# Schematics_5.net
KiCad netlist of a schematic drawn in Altium Designer
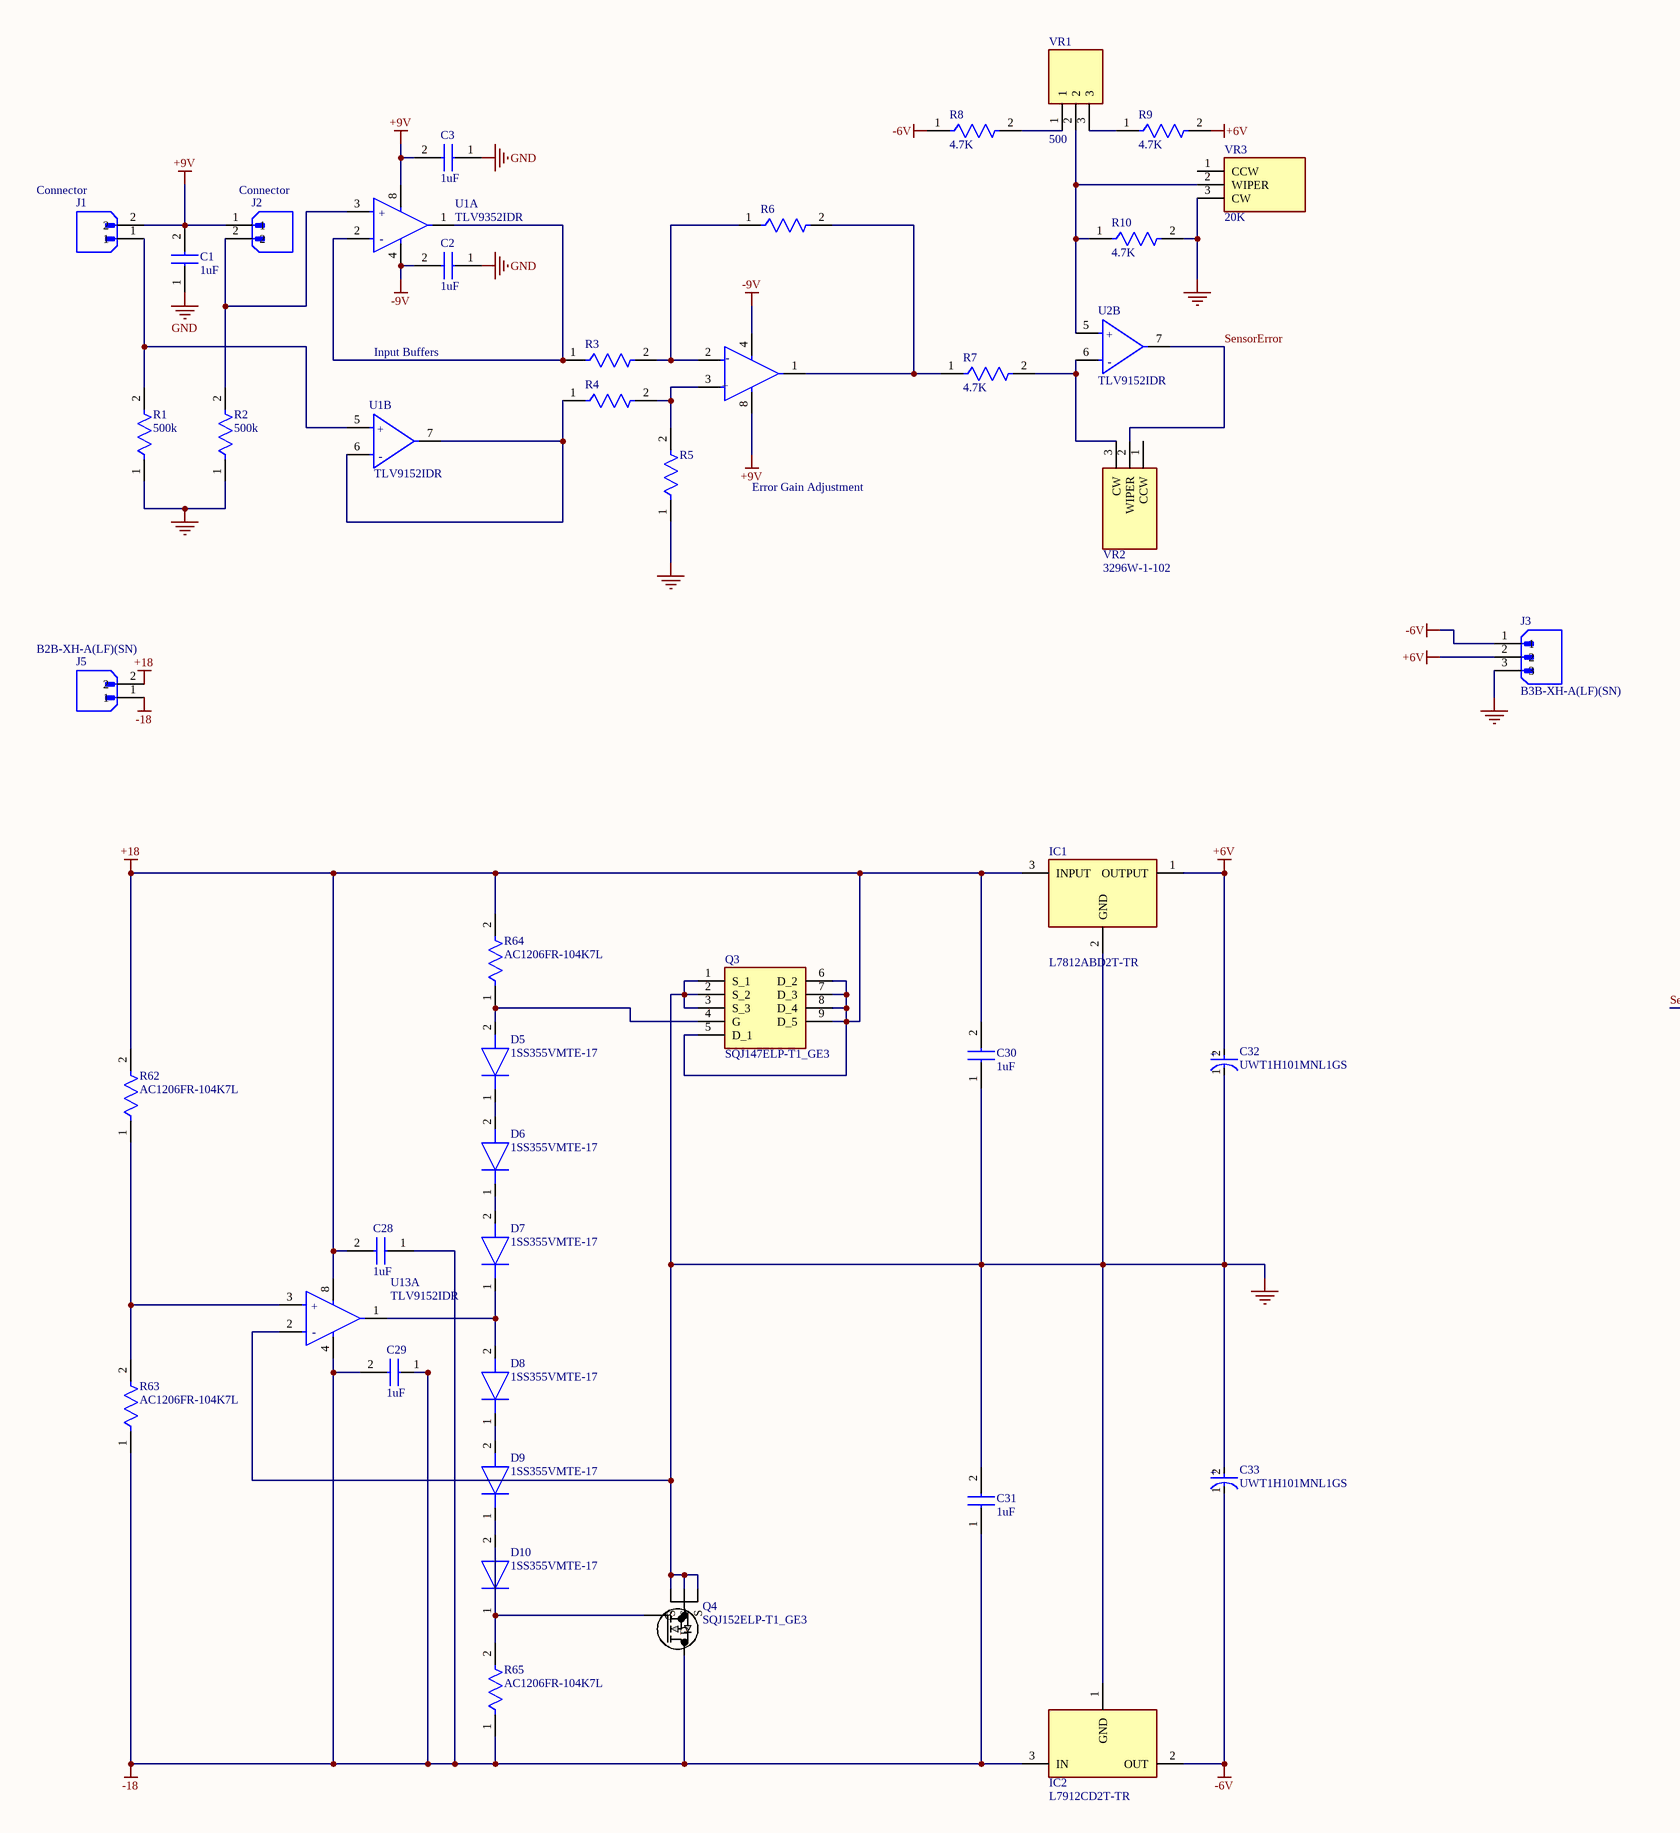
[diagram p0: Schematics_5.SchDoc, top left]
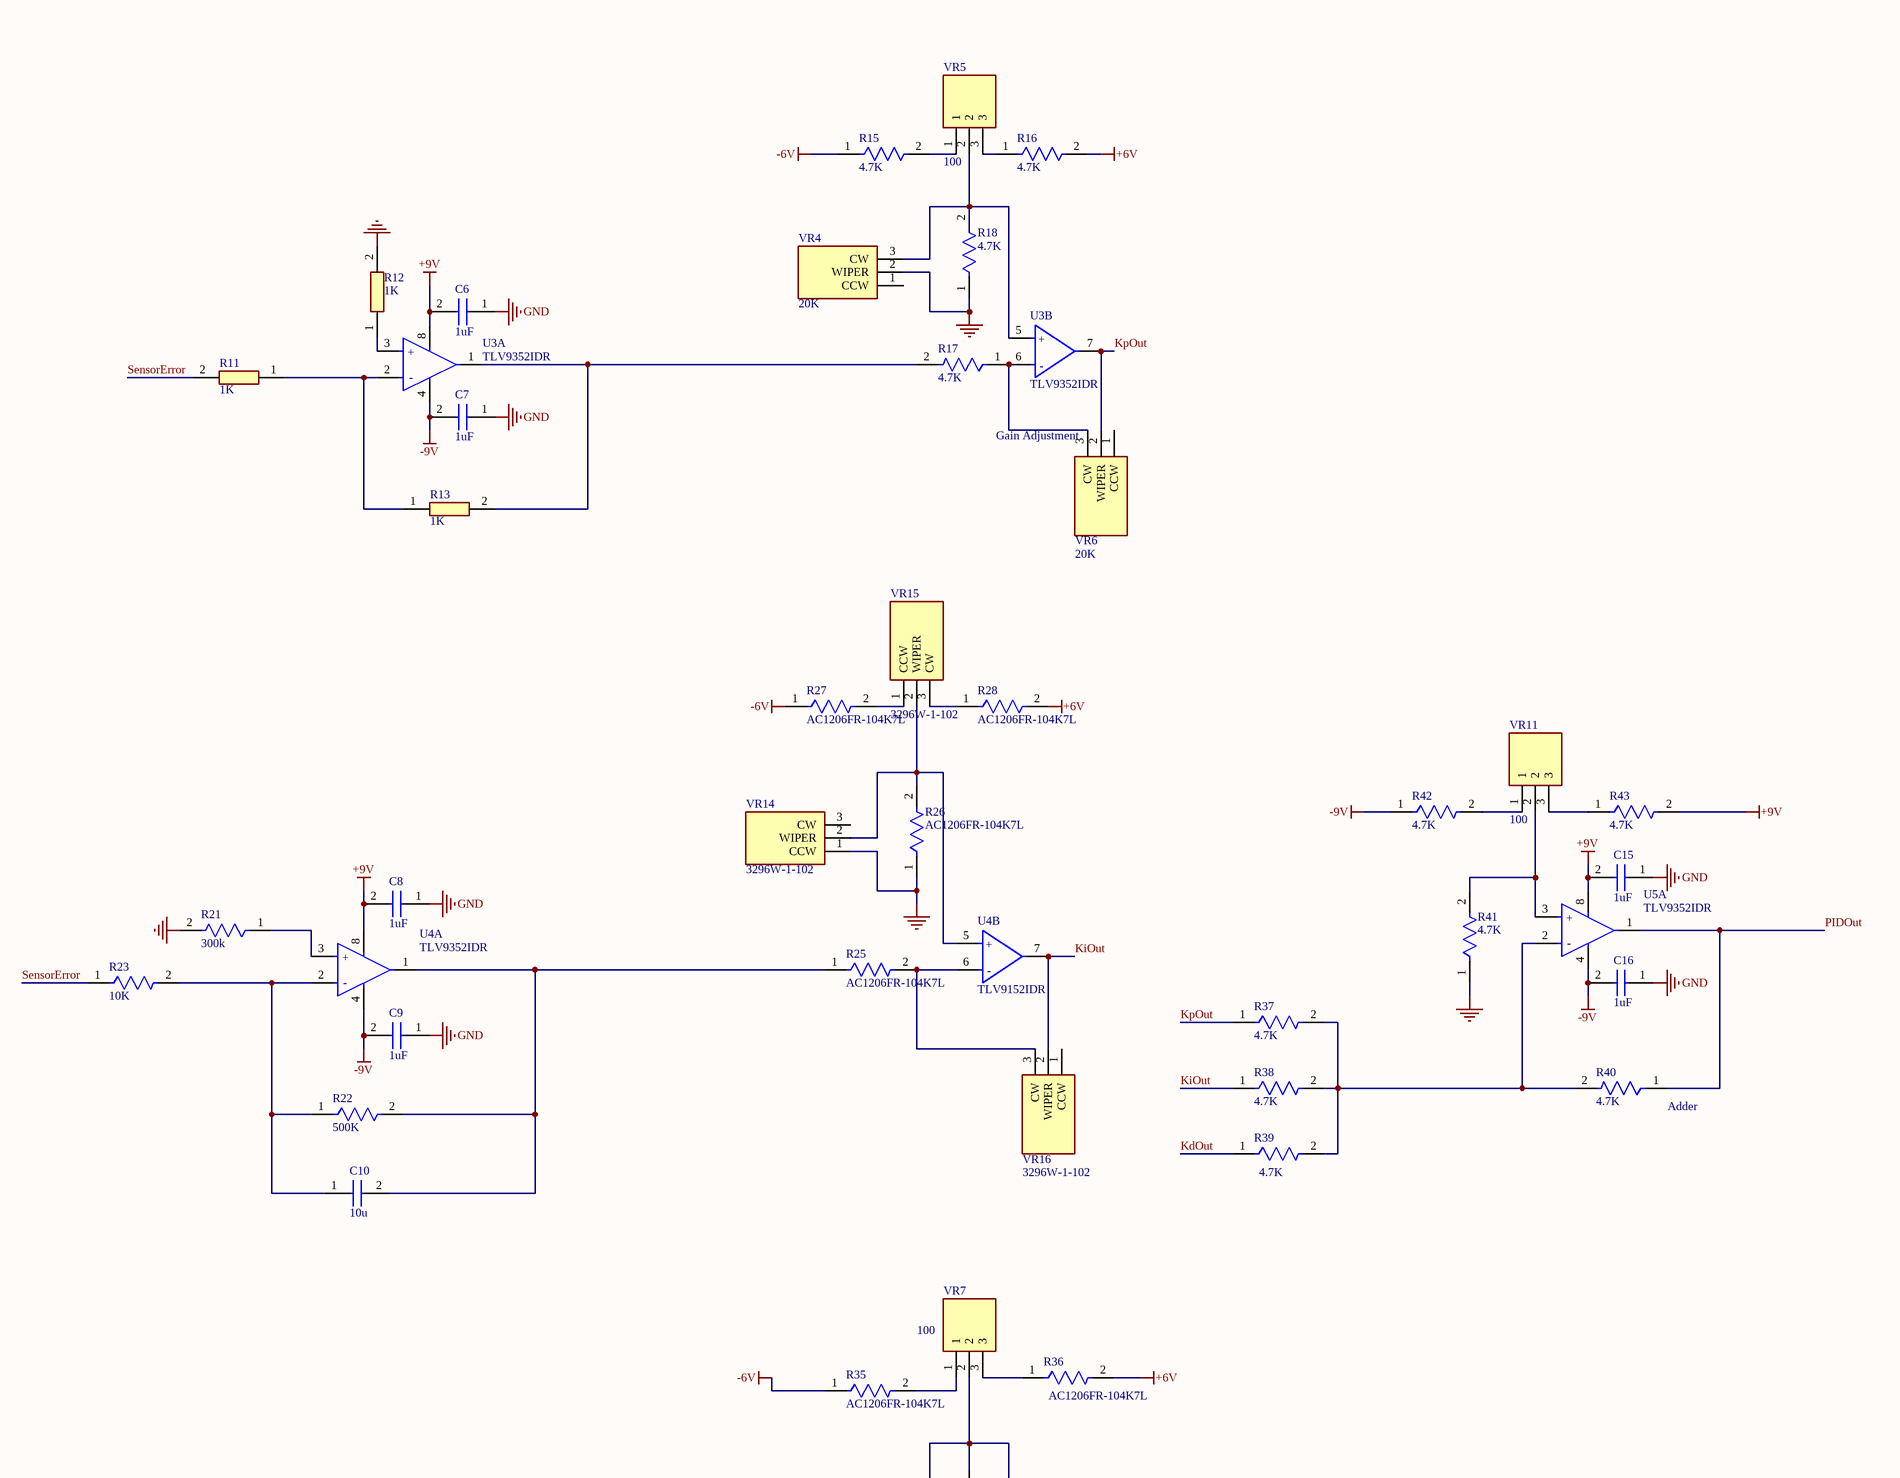
[diagram p1: Schematics_5.SchDoc, top right]
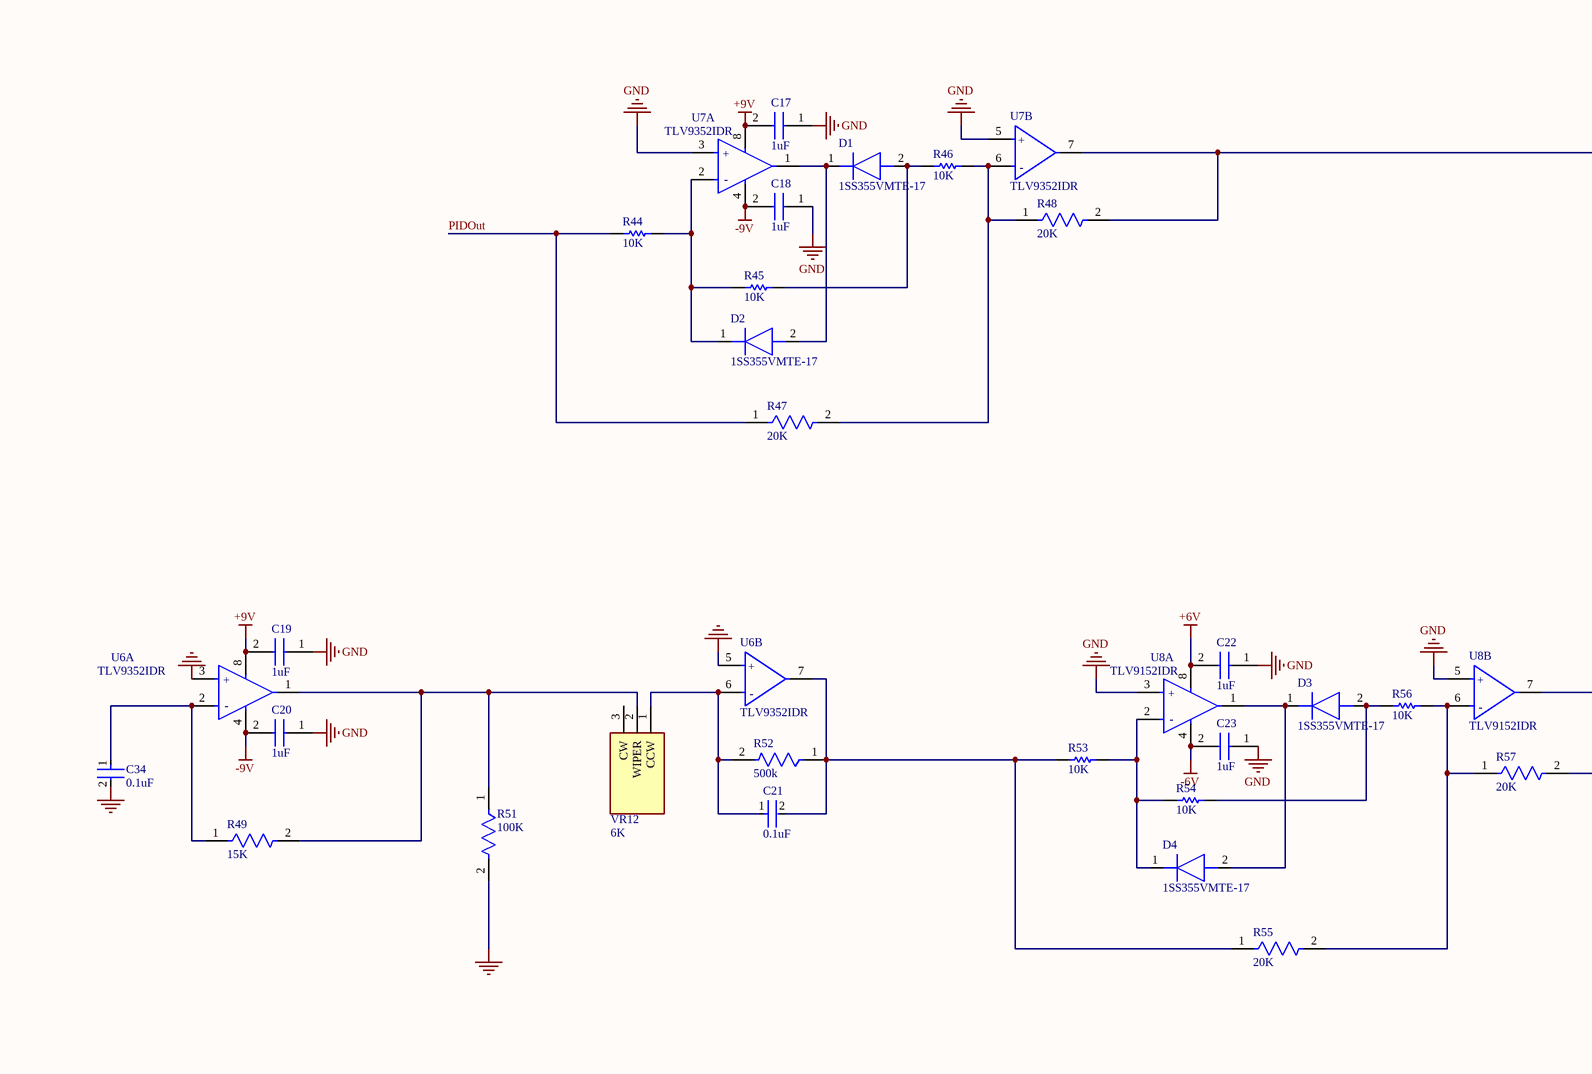
[diagram p2: Schematics_5.SchDoc, bottom left]
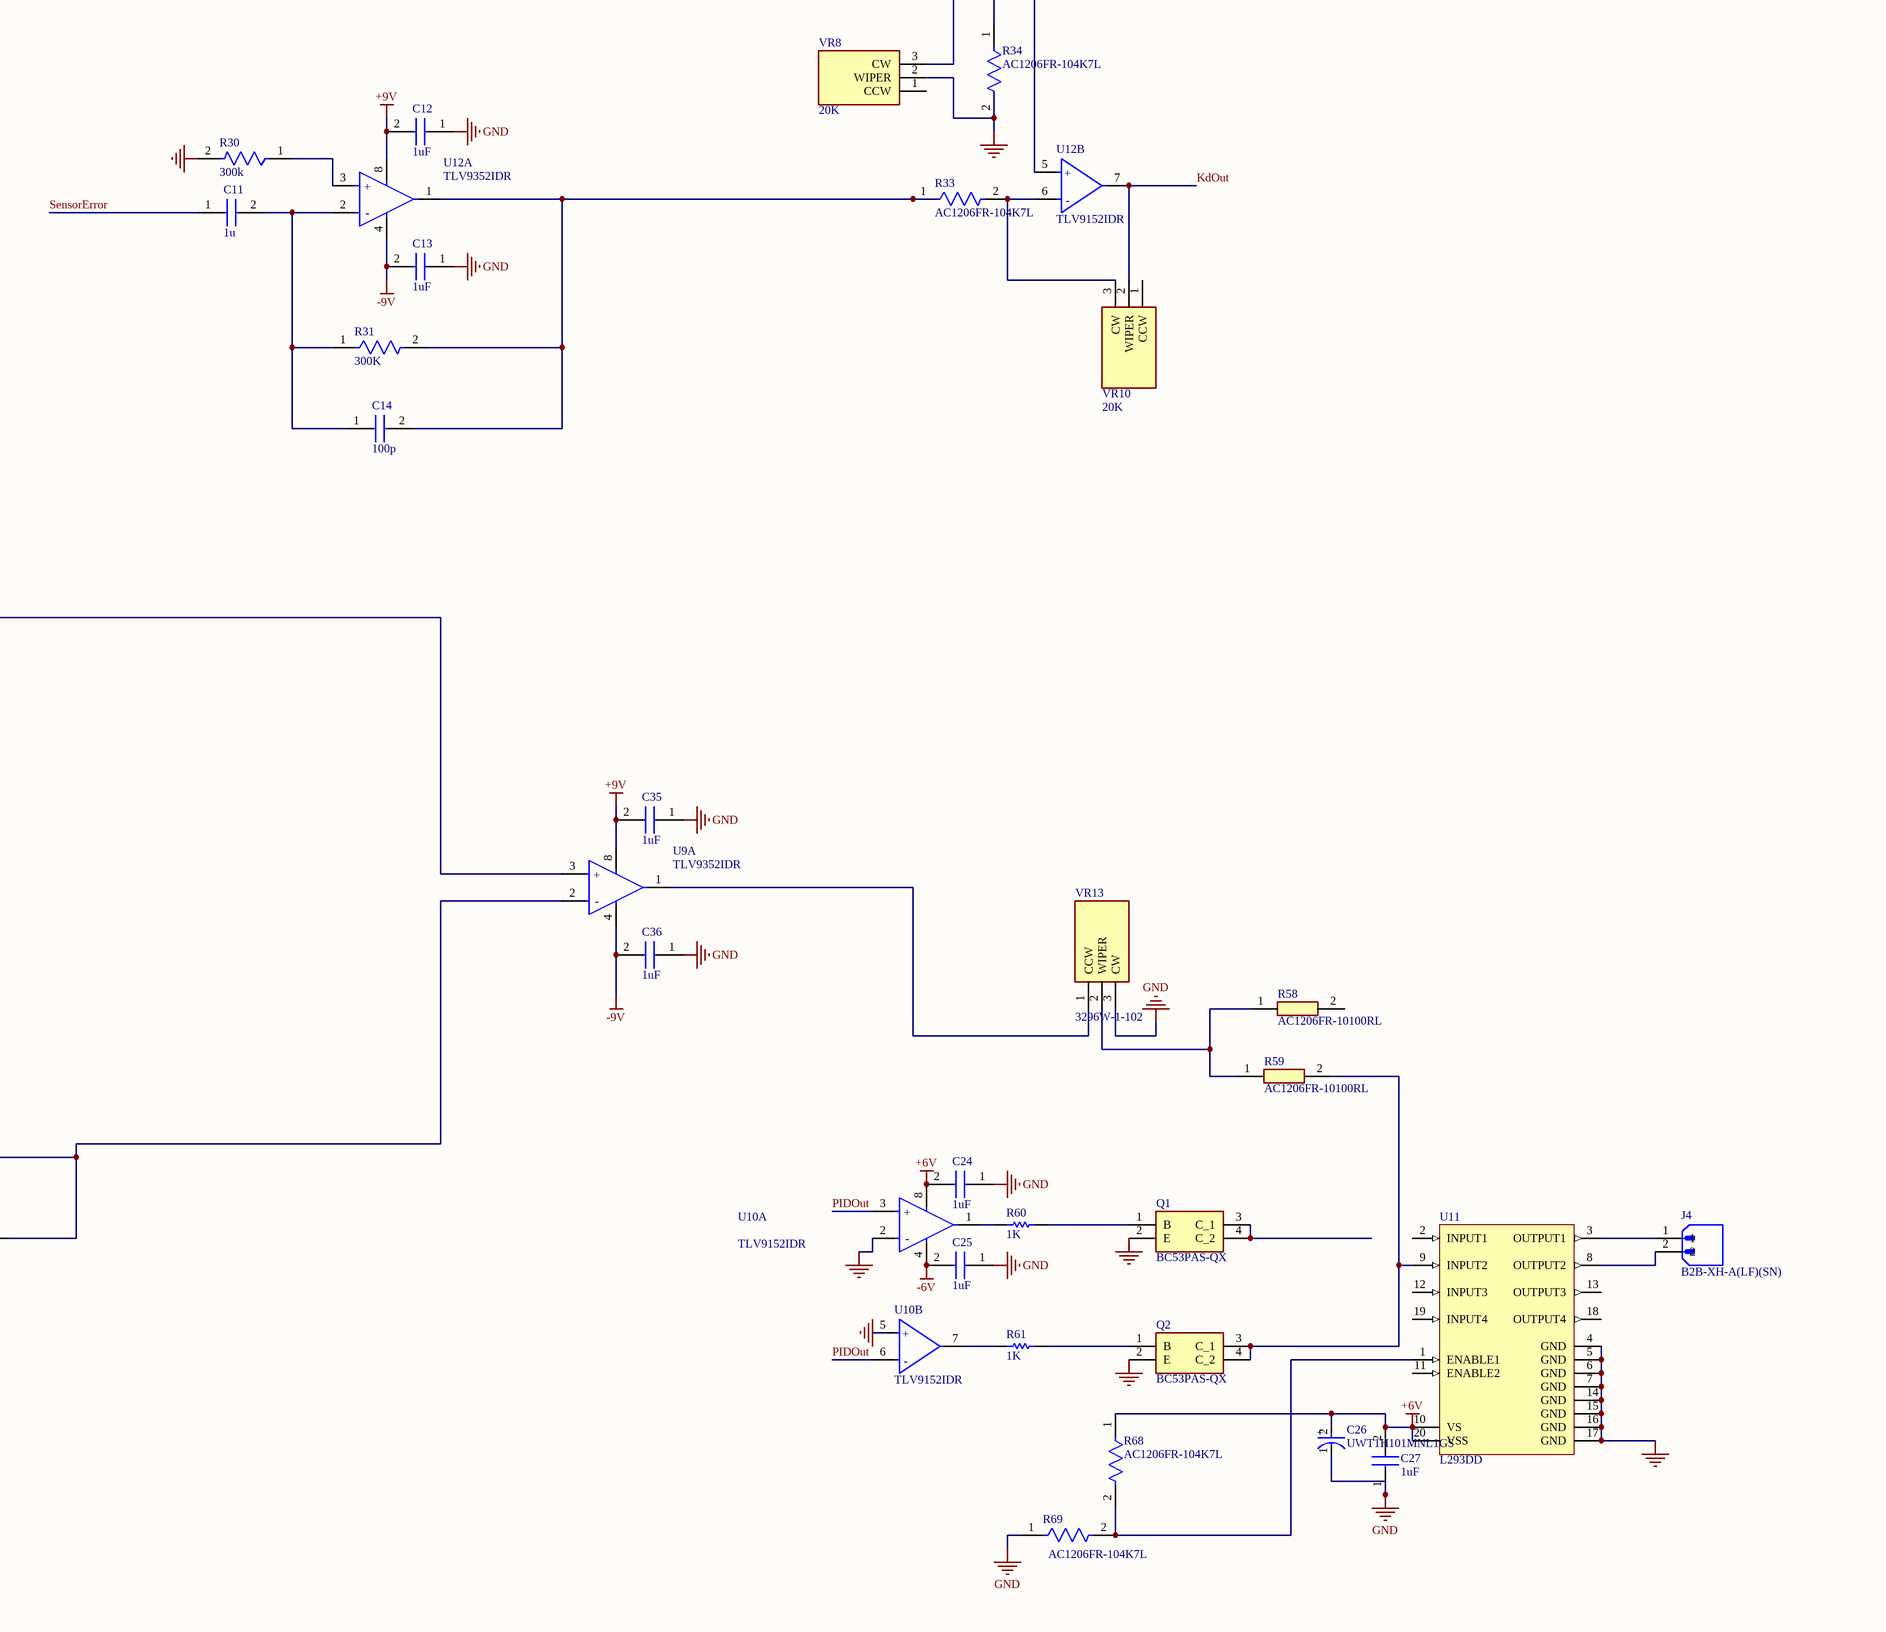
[diagram p3: Schematics_5.SchDoc, bottom right]

(export (version "E")
  (design (tool "Eeschema 10.0.6"))
  (components
    (comp (ref "C1")
      (value "1uF")
      (footprint "SamacSys:CAPC3216X178N")
      (description "Capacitor 12063C105MAT2A")
      (fields
        (field (name "MANUFACTURER_PART_NUMBER") "12063C105MAT2A")
        (field (name "MOUSER PART NUMBER") "581-12063C105MAT2A")
      )
      (libsource (lib "*") (part "12063C105MAT2A"))
    )
    (comp (ref "C2")
      (value "1uF")
      (footprint "SamacSys:CAPC3216X178N")
      (description "Capacitor 12063C105MAT2A")
      (fields
        (field (name "MANUFACTURER_PART_NUMBER") "12063C105MAT2A")
        (field (name "MOUSER PART NUMBER") "581-12063C105MAT2A")
      )
      (libsource (lib "*") (part "12063C105MAT2A"))
    )
    (comp (ref "C3")
      (value "1uF")
      (footprint "SamacSys:CAPC3216X178N")
      (description "Capacitor 12063C105MAT2A")
      (fields
        (field (name "MANUFACTURER_PART_NUMBER") "12063C105MAT2A")
        (field (name "MOUSER PART NUMBER") "581-12063C105MAT2A")
      )
      (libsource (lib "*") (part "12063C105MAT2A"))
    )
    (comp (ref "C6")
      (value "1uF")
      (footprint "SamacSys:CAPC3216X178N")
      (description "Capacitor 12063C105MAT2A")
      (fields
        (field (name "MANUFACTURER_PART_NUMBER") "12063C105MAT2A")
        (field (name "MOUSER PART NUMBER") "581-12063C105MAT2A")
      )
      (libsource (lib "*") (part "12063C105MAT2A"))
    )
    (comp (ref "C7")
      (value "1uF")
      (footprint "SamacSys:CAPC3216X178N")
      (description "Capacitor 12063C105MAT2A")
      (fields
        (field (name "MANUFACTURER_PART_NUMBER") "12063C105MAT2A")
        (field (name "MOUSER PART NUMBER") "581-12063C105MAT2A")
      )
      (libsource (lib "*") (part "12063C105MAT2A"))
    )
    (comp (ref "C8")
      (value "1uF")
      (footprint "SamacSys:CAPC3216X178N")
      (description "Capacitor 12063C105MAT2A")
      (fields
        (field (name "MANUFACTURER_PART_NUMBER") "12063C105MAT2A")
        (field (name "MOUSER PART NUMBER") "581-12063C105MAT2A")
      )
      (libsource (lib "*") (part "12063C105MAT2A"))
    )
    (comp (ref "C9")
      (value "1uF")
      (footprint "SamacSys:CAPC3216X178N")
      (description "Capacitor 12063C105MAT2A")
      (fields
        (field (name "MANUFACTURER_PART_NUMBER") "12063C105MAT2A")
        (field (name "MOUSER PART NUMBER") "581-12063C105MAT2A")
      )
      (libsource (lib "*") (part "12063C105MAT2A"))
    )
    (comp (ref "C10")
      (value "10u")
      (footprint "SamacSys:CAPC3216X170N")
      (description "Capacitor")
      (fields
        (field (name "MANUFACTURER_PART_NUMBER") "VJ1206A101JXEAT")
        (field (name "MOUSER PART NUMBER") "77-VJ1206A101JXEAT")
      )
      (libsource (lib "SamacSys") (part "VJ1206A101JXEAT"))
    )
    (comp (ref "C11")
      (value "1u")
      (footprint "SamacSys:C1206_FT")
      (description "Capacitor")
      (fields
        (field (name "MANUFACTURER_PART_NUMBER") "C1206X105J1RACTU")
        (field (name "MOUSER PART NUMBER") "80-C1206X105J1R")
      )
      (libsource (lib "*") (part "C1206X105J1RACTU"))
    )
    (comp (ref "C12")
      (value "1uF")
      (footprint "SamacSys:CAPC3216X178N")
      (description "Capacitor 12063C105MAT2A")
      (fields
        (field (name "MANUFACTURER_PART_NUMBER") "12063C105MAT2A")
        (field (name "MOUSER PART NUMBER") "581-12063C105MAT2A")
      )
      (libsource (lib "*") (part "12063C105MAT2A"))
    )
    (comp (ref "C13")
      (value "1uF")
      (footprint "SamacSys:CAPC3216X178N")
      (description "Capacitor 12063C105MAT2A")
      (fields
        (field (name "MANUFACTURER_PART_NUMBER") "12063C105MAT2A")
        (field (name "MOUSER PART NUMBER") "581-12063C105MAT2A")
      )
      (libsource (lib "*") (part "12063C105MAT2A"))
    )
    (comp (ref "C14")
      (value "100p")
      (footprint "SamacSys:CAPC3216X170N")
      (description "Capacitor")
      (fields
        (field (name "MANUFACTURER_PART_NUMBER") "VJ1206A101JXEAT")
        (field (name "MOUSER PART NUMBER") "77-VJ1206A101JXEAT")
      )
      (libsource (lib "*") (part "VJ1206A101JXEAT"))
    )
    (comp (ref "C15")
      (value "1uF")
      (footprint "SamacSys:CAPC3216X178N")
      (description "Capacitor 12063C105MAT2A")
      (fields
        (field (name "MANUFACTURER_PART_NUMBER") "12063C105MAT2A")
        (field (name "MOUSER PART NUMBER") "581-12063C105MAT2A")
      )
      (libsource (lib "*") (part "12063C105MAT2A"))
    )
    (comp (ref "C16")
      (value "1uF")
      (footprint "SamacSys:CAPC3216X178N")
      (description "Capacitor 12063C105MAT2A")
      (fields
        (field (name "MANUFACTURER_PART_NUMBER") "12063C105MAT2A")
        (field (name "MOUSER PART NUMBER") "581-12063C105MAT2A")
      )
      (libsource (lib "*") (part "12063C105MAT2A"))
    )
    (comp (ref "C17")
      (value "1uF")
      (footprint "SamacSys:CAPC3216X178N")
      (description "Capacitor 12063C105MAT2A")
      (fields
        (field (name "MANUFACTURER_PART_NUMBER") "12063C105MAT2A")
        (field (name "MOUSER PART NUMBER") "581-12063C105MAT2A")
      )
      (libsource (lib "*") (part "12063C105MAT2A"))
    )
    (comp (ref "C18")
      (value "1uF")
      (footprint "SamacSys:CAPC3216X178N")
      (description "Capacitor 12063C105MAT2A")
      (fields
        (field (name "MANUFACTURER_PART_NUMBER") "12063C105MAT2A")
        (field (name "MOUSER PART NUMBER") "581-12063C105MAT2A")
      )
      (libsource (lib "*") (part "12063C105MAT2A"))
    )
    (comp (ref "C19")
      (value "1uF")
      (footprint "SamacSys:CAPC3216X178N")
      (description "Capacitor 12063C105MAT2A")
      (fields
        (field (name "MANUFACTURER_PART_NUMBER") "12063C105MAT2A")
        (field (name "MOUSER PART NUMBER") "581-12063C105MAT2A")
      )
      (libsource (lib "*") (part "12063C105MAT2A"))
    )
    (comp (ref "C20")
      (value "1uF")
      (footprint "SamacSys:CAPC3216X178N")
      (description "Capacitor 12063C105MAT2A")
      (fields
        (field (name "MANUFACTURER_PART_NUMBER") "12063C105MAT2A")
        (field (name "MOUSER PART NUMBER") "581-12063C105MAT2A")
      )
      (libsource (lib "*") (part "12063C105MAT2A"))
    )
    (comp (ref "C21")
      (value "0.1uF")
      (footprint "FP-C1206C-EB-MFG")
      (description "CAP CER 0.1UF 25V C0G/NP0 1206")
      (fields
        (field (name "MANUFACTURER") "KEMET")
        (field (name "MANUFACTURER PART NUMBER") "C1206C104F3GACTU")
      )
      (libsource (lib "Altium Content Vault") (part "b4654b650e69147ec39a6b967a45e02"))
    )
    (comp (ref "C22")
      (value "1uF")
      (footprint "SamacSys:CAPC3216X178N")
      (description "Capacitor 12063C105MAT2A")
      (fields
        (field (name "MANUFACTURER_PART_NUMBER") "12063C105MAT2A")
        (field (name "MOUSER PART NUMBER") "581-12063C105MAT2A")
      )
      (libsource (lib "*") (part "12063C105MAT2A"))
    )
    (comp (ref "C23")
      (value "1uF")
      (footprint "SamacSys:CAPC3216X178N")
      (description "Capacitor 12063C105MAT2A")
      (fields
        (field (name "MANUFACTURER_PART_NUMBER") "12063C105MAT2A")
        (field (name "MOUSER PART NUMBER") "581-12063C105MAT2A")
      )
      (libsource (lib "*") (part "12063C105MAT2A"))
    )
    (comp (ref "C24")
      (value "1uF")
      (footprint "SamacSys:CAPC3216X178N")
      (description "Capacitor 12063C105MAT2A")
      (fields
        (field (name "MANUFACTURER_PART_NUMBER") "12063C105MAT2A")
        (field (name "MOUSER PART NUMBER") "581-12063C105MAT2A")
      )
      (libsource (lib "*") (part "12063C105MAT2A"))
    )
    (comp (ref "C25")
      (value "1uF")
      (footprint "SamacSys:CAPC3216X178N")
      (description "Capacitor 12063C105MAT2A")
      (fields
        (field (name "MANUFACTURER_PART_NUMBER") "12063C105MAT2A")
        (field (name "MOUSER PART NUMBER") "581-12063C105MAT2A")
      )
      (libsource (lib "*") (part "12063C105MAT2A"))
    )
    (comp (ref "C26")
      (value "UWT1H101MNL1GS")
      (footprint "FP-UWT1H101MNL1GS-MFG")
      (description "CAP ALUM 100UF 20% 50V SMD")
      (fields (field (name "TOLERANCE") "20%") (field (name "VOLTAGE") "50V"))
      (libsource (lib "Altium Content Vault") (part "203bc49f2ac43e59fd269a8c329ed05"))
    )
    (comp (ref "C27")
      (value "1uF")
      (footprint "SamacSys:CAPC3216X178N")
      (description "Capacitor 12063C105MAT2A")
      (fields
        (field (name "MANUFACTURER_PART_NUMBER") "12063C105MAT2A")
        (field (name "MOUSER PART NUMBER") "581-12063C105MAT2A")
      )
      (libsource (lib "*") (part "12063C105MAT2A"))
    )
    (comp (ref "C28")
      (value "1uF")
      (footprint "SamacSys:CAPC3216X178N")
      (description "Capacitor 12063C105MAT2A")
      (fields
        (field (name "MANUFACTURER_PART_NUMBER") "12063C105MAT2A")
        (field (name "MOUSER PART NUMBER") "581-12063C105MAT2A")
      )
      (libsource (lib "*") (part "12063C105MAT2A"))
    )
    (comp (ref "C29")
      (value "1uF")
      (footprint "SamacSys:CAPC3216X178N")
      (description "Capacitor 12063C105MAT2A")
      (fields
        (field (name "MANUFACTURER_PART_NUMBER") "12063C105MAT2A")
        (field (name "MOUSER PART NUMBER") "581-12063C105MAT2A")
      )
      (libsource (lib "*") (part "12063C105MAT2A"))
    )
    (comp (ref "C30")
      (value "1uF")
      (footprint "SamacSys:CAPC3216X178N")
      (description "Capacitor 12063C105MAT2A")
      (fields
        (field (name "MANUFACTURER_PART_NUMBER") "12063C105MAT2A")
        (field (name "MOUSER PART NUMBER") "581-12063C105MAT2A")
      )
      (libsource (lib "*") (part "12063C105MAT2A"))
    )
    (comp (ref "C31")
      (value "1uF")
      (footprint "SamacSys:CAPC3216X178N")
      (description "Capacitor 12063C105MAT2A")
      (fields
        (field (name "MANUFACTURER_PART_NUMBER") "12063C105MAT2A")
        (field (name "MOUSER PART NUMBER") "581-12063C105MAT2A")
      )
      (libsource (lib "*") (part "12063C105MAT2A"))
    )
    (comp (ref "C32")
      (value "UWT1H101MNL1GS")
      (footprint "FP-UWT1H101MNL1GS-MFG")
      (description "CAP ALUM 100UF 20% 50V SMD")
      (fields (field (name "TOLERANCE") "20%") (field (name "VOLTAGE") "50V"))
      (libsource (lib "Altium Content Vault") (part "203bc49f2ac43e59fd269a8c329ed05"))
    )
    (comp (ref "C33")
      (value "UWT1H101MNL1GS")
      (footprint "FP-UWT1H101MNL1GS-MFG")
      (description "CAP ALUM 100UF 20% 50V SMD")
      (fields (field (name "TOLERANCE") "20%") (field (name "VOLTAGE") "50V"))
      (libsource (lib "Altium Content Vault") (part "203bc49f2ac43e59fd269a8c329ed05"))
    )
    (comp (ref "C34")
      (value "0.1uF")
      (footprint "FP-C1206C-EB-MFG")
      (description "CAP CER 0.1UF 25V C0G/NP0 1206")
      (fields
        (field (name "MANUFACTURER") "KEMET")
        (field (name "MANUFACTURER PART NUMBER") "C1206C104F3GACTU")
      )
      (libsource (lib "Altium Content Vault") (part "b4654b650e69147ec39a6b967a45e02"))
    )
    (comp (ref "C35")
      (value "1uF")
      (footprint "SamacSys:CAPC3216X178N")
      (description "Capacitor 12063C105MAT2A")
      (fields
        (field (name "MANUFACTURER_PART_NUMBER") "12063C105MAT2A")
        (field (name "MOUSER PART NUMBER") "581-12063C105MAT2A")
      )
      (libsource (lib "*") (part "12063C105MAT2A"))
    )
    (comp (ref "C36")
      (value "1uF")
      (footprint "SamacSys:CAPC3216X178N")
      (description "Capacitor 12063C105MAT2A")
      (fields
        (field (name "MANUFACTURER_PART_NUMBER") "12063C105MAT2A")
        (field (name "MOUSER PART NUMBER") "581-12063C105MAT2A")
      )
      (libsource (lib "*") (part "12063C105MAT2A"))
    )
    (comp (ref "D1")
      (value "1SS355VMTE-17")
      (footprint "SamacSys:UDZVTE1722B")
      (description "Diode")
      (fields (field (name "MOUSER PART NUMBER") "755-1SS355VMTE-17"))
      (libsource (lib "*") (part "1SS355VMTE-17"))
    )
    (comp (ref "D2")
      (value "1SS355VMTE-17")
      (footprint "SamacSys:UDZVTE1722B")
      (description "Diode")
      (fields (field (name "MOUSER PART NUMBER") "755-1SS355VMTE-17"))
      (libsource (lib "*") (part "1SS355VMTE-17"))
    )
    (comp (ref "D3")
      (value "1SS355VMTE-17")
      (footprint "SamacSys:UDZVTE1722B")
      (description "Diode")
      (fields (field (name "MOUSER PART NUMBER") "755-1SS355VMTE-17"))
      (libsource (lib "*") (part "1SS355VMTE-17"))
    )
    (comp (ref "D4")
      (value "1SS355VMTE-17")
      (footprint "SamacSys:UDZVTE1722B")
      (description "Diode")
      (fields (field (name "MOUSER PART NUMBER") "755-1SS355VMTE-17"))
      (libsource (lib "*") (part "1SS355VMTE-17"))
    )
    (comp (ref "D5")
      (value "1SS355VMTE-17")
      (footprint "SamacSys:UDZVTE1722B")
      (description "Diode")
      (fields (field (name "MOUSER PART NUMBER") "755-1SS355VMTE-17"))
      (libsource (lib "SamacSys") (part "1SS355VMTE-17"))
    )
    (comp (ref "D6")
      (value "1SS355VMTE-17")
      (footprint "SamacSys:UDZVTE1722B")
      (description "Diode")
      (fields (field (name "MOUSER PART NUMBER") "755-1SS355VMTE-17"))
      (libsource (lib "SamacSys") (part "1SS355VMTE-17"))
    )
    (comp (ref "D7")
      (value "1SS355VMTE-17")
      (footprint "SamacSys:UDZVTE1722B")
      (description "Diode")
      (fields (field (name "MOUSER PART NUMBER") "755-1SS355VMTE-17"))
      (libsource (lib "SamacSys") (part "1SS355VMTE-17"))
    )
    (comp (ref "D8")
      (value "1SS355VMTE-17")
      (footprint "SamacSys:UDZVTE1722B")
      (description "Diode")
      (fields (field (name "MOUSER PART NUMBER") "755-1SS355VMTE-17"))
      (libsource (lib "SamacSys") (part "1SS355VMTE-17"))
    )
    (comp (ref "D9")
      (value "1SS355VMTE-17")
      (footprint "SamacSys:UDZVTE1722B")
      (description "Diode")
      (fields (field (name "MOUSER PART NUMBER") "755-1SS355VMTE-17"))
      (libsource (lib "SamacSys") (part "1SS355VMTE-17"))
    )
    (comp (ref "D10")
      (value "1SS355VMTE-17")
      (footprint "SamacSys:UDZVTE1722B")
      (description "Diode")
      (fields (field (name "MOUSER PART NUMBER") "755-1SS355VMTE-17"))
      (libsource (lib "SamacSys") (part "1SS355VMTE-17"))
    )
    (comp (ref "IC1")
      (value "L7812ABD2T-TR")
      (footprint "SamacSys:L7812ABD2TTR")
      (description "Integrated Circuit")
      (fields (field (name "MOUSER PART NUMBER") "511-L7812ABD2T-TR"))
      (libsource (lib "SamacSys") (part "L7812ABD2T-TR"))
    )
    (comp (ref "IC2")
      (value "L7912CD2T-TR")
      (footprint "SamacSys:L7905CD2TTR")
      (description "Integrated Circuit")
      (fields (field (name "MOUSER PART NUMBER") "511-L7912CD2T-TR"))
      (libsource (lib "SamacSys") (part "L7912CD2T-TR"))
    )
    (comp (ref "J1")
      (value "Connector")
      (footprint "JST_B2B-XH-A(LF)(SN)")
      (description "Connector Header Through Hole 2 position 0.098 (2.50mm)")
      (fields (field (name "MF") "JST Sales America Inc.") (field (name "MP") "B2B-XH-A(LF)(SN)"))
      (libsource (lib "B2B-XH-A_LF__SN_") (part "B2B-XH-A(LF)(SN)"))
    )
    (comp (ref "J2")
      (value "Connector")
      (footprint "JST_B2B-XH-A(LF)(SN)")
      (description "Connector Header Through Hole 2 position 0.098 (2.50mm)")
      (fields (field (name "MF") "JST Sales America Inc.") (field (name "MP") "B2B-XH-A(LF)(SN)"))
      (libsource (lib "") (part "B2B-XH-A(LF)(SN)_1"))
    )
    (comp (ref "J3")
      (value "B3B-XH-A(LF)(SN)")
      (footprint "JST_B3B-XH-A(LF)(SN)")
      (description "Connector Header Through Hole 3 position 0.098 (2.50mm)")
      (fields (field (name "MF") "JST Sales"))
      (libsource (lib "B3B-XH-A_LF__SN_") (part "B3B-XH-A(LF)(SN)"))
    )
    (comp (ref "J4")
      (value "B2B-XH-A(LF)(SN)")
      (footprint "JST_B2B-XH-A(LF)(SN)")
      (description "Connector Header Through Hole 2 position 0.098 (2.50mm)")
      (fields (field (name "MF") "JST Sales America Inc."))
      (libsource (lib "") (part "B2B-XH-A(LF)(SN)_1"))
    )
    (comp (ref "J5")
      (value "B2B-XH-A(LF)(SN)")
      (footprint "JST_B2B-XH-A(LF)(SN)")
      (description "Connector Header Through Hole 2 position 0.098 (2.50mm)")
      (fields (field (name "MF") "JST Sales America Inc."))
      (libsource (lib "B2B-XH-A_LF__SN_") (part "B2B-XH-A(LF)(SN)"))
    )
    (comp (ref "Q1")
      (value "BC53PAS-QX")
      (footprint "SamacSys:BC53PASQX")
      (description "Transistor BJT PNP")
      (fields (field (name "MOUSER PART NUMBER") "771-BC53PAS-QX"))
      (libsource (lib "*") (part "BC53PAS-QX"))
    )
    (comp (ref "Q2")
      (value "BC53PAS-QX")
      (footprint "SamacSys:BC53PASQX")
      (description "Transistor BJT PNP")
      (fields (field (name "MOUSER PART NUMBER") "771-BC53PAS-QX"))
      (libsource (lib "*") (part "BC53PAS-QX"))
    )
    (comp (ref "Q3")
      (value "SQJ147ELP-T1_GE3")
      (footprint "SamacSys:SQJ147ELPT1_GE3")
      (description "MOSFET (N-Channel)")
      (fields (field (name "MOUSER PART NUMBER") "78-SQJ147ELP-T1_GE3"))
      (libsource (lib "*") (part "SQJ147ELP-T1_GE3"))
    )
    (comp (ref "Q4")
      (value "SQJ152ELP-T1_GE3")
      (footprint "DPAK5_ELP-T1_GE3_VIS")
      (description "No Description Available")
      (fields (field (name "COPYRIGHT") "Copyright (C) 2023 Ultra Librarian. All rights reserved."))
      (libsource (lib "SQJ152ELP-T1_GE3") (part "SQJ152ELP-T1_GE3"))
    )
    (comp (ref "R1")
      (value "500k")
      (footprint "FP-CRMA1206-IPC_A")
      (description "CRMA1206AF500KFKEF Res Thick Film 1206 500K Ohm 1% 0.3W ±100ppm/C Pad SMD Automotive T/R")
      (fields (field (name "TOLERANCE") "1%"))
      (libsource (lib "Altium Content Vault") (part "1029c3af85768c4190bb7ad29bc67b5"))
    )
    (comp (ref "R2")
      (value "500k")
      (footprint "FP-CRMA1206-IPC_A")
      (description "CRMA1206AF500KFKEF Res Thick Film 1206 500K Ohm 1% 0.3W ±100ppm/C Pad SMD Automotive T/R")
      (fields (field (name "TOLERANCE") "1%"))
      (libsource (lib "Altium Content Vault") (part "1029c3af85768c4190bb7ad29bc67b5"))
    )
    (comp (ref "R3")
      (value "4.7K")
      (footprint "FP-AC1206-MFG")
      (description "AC1206 4.7KΩ 0.25W 1.00%")
      (fields
        (field (name "OCTOPART") "https://octopart.com/ac1206fr-104k7l-yageo-84718857")
        (field (name "TOLERANCE") "0.01")
      )
      (libsource (lib "Altium Content Vault") (part "1029c3af85768c4190bb7ad29bc67b5"))
    )
    (comp (ref "R4")
      (value "4.7K")
      (footprint "FP-AC1206-MFG")
      (description "AC1206 4.7KΩ 0.25W 1.00%")
      (fields
        (field (name "OCTOPART") "https://octopart.com/ac1206fr-104k7l-yageo-84718857")
        (field (name "TOLERANCE") "0.01")
      )
      (libsource (lib "Altium Content Vault") (part "1029c3af85768c4190bb7ad29bc67b5"))
    )
    (comp (ref "R5")
      (value "4.7K")
      (footprint "FP-AC1206-MFG")
      (description "AC1206 4.7KΩ 0.25W 1.00%")
      (fields
        (field (name "OCTOPART") "https://octopart.com/ac1206fr-104k7l-yageo-84718857")
        (field (name "TOLERANCE") "0.01")
      )
      (libsource (lib "Altium Content Vault") (part "1029c3af85768c4190bb7ad29bc67b5"))
    )
    (comp (ref "R6")
      (value "4.7K")
      (footprint "FP-AC1206-MFG")
      (description "AC1206 4.7KΩ 0.25W 1.00%")
      (fields
        (field (name "OCTOPART") "https://octopart.com/ac1206fr-104k7l-yageo-84718857")
        (field (name "TOLERANCE") "0.01")
      )
      (libsource (lib "Altium Content Vault") (part "1029c3af85768c4190bb7ad29bc67b5"))
    )
    (comp (ref "R7")
      (value "4.7K")
      (footprint "FP-AC1206-MFG")
      (description "AC1206 4.7KΩ 0.25W 1.00%")
      (fields
        (field (name "OCTOPART") "https://octopart.com/ac1206fr-104k7l-yageo-84718857")
        (field (name "TOLERANCE") "0.01")
      )
      (libsource (lib "Altium Content Vault") (part "1029c3af85768c4190bb7ad29bc67b5"))
    )
    (comp (ref "R8")
      (value "4.7K")
      (footprint "FP-AC1206-MFG")
      (description "AC1206 4.7KΩ 0.25W 1.00%")
      (fields
        (field (name "OCTOPART") "https://octopart.com/ac1206fr-104k7l-yageo-84718857")
        (field (name "TOLERANCE") "0.01")
      )
      (libsource (lib "Altium Content Vault") (part "1029c3af85768c4190bb7ad29bc67b5"))
    )
    (comp (ref "R9")
      (value "4.7K")
      (footprint "FP-AC1206-MFG")
      (description "AC1206 4.7KΩ 0.25W 1.00%")
      (fields
        (field (name "OCTOPART") "https://octopart.com/ac1206fr-104k7l-yageo-84718857")
        (field (name "TOLERANCE") "0.01")
      )
      (libsource (lib "Altium Content Vault") (part "1029c3af85768c4190bb7ad29bc67b5"))
    )
    (comp (ref "R10")
      (value "4.7K")
      (footprint "FP-AC1206-MFG")
      (description "AC1206 4.7KΩ 0.25W 1.00%")
      (fields
        (field (name "OCTOPART") "https://octopart.com/ac1206fr-104k7l-yageo-84718857")
        (field (name "TOLERANCE") "0.01")
      )
      (libsource (lib "Altium Content Vault") (part "1029c3af85768c4190bb7ad29bc67b5"))
    )
    (comp (ref "R11")
      (value "1K")
      (footprint "SamacSys:RESC3116X65N")
      (description "1K resistor 1206")
      (fields
        (field (name "MANUFACTURER_PART_NUMBER") "CRM1206QFX-1001ELF")
        (field (name "MOUSER PART NUMBER") "652-CRM1206QFX-1001E")
      )
      (libsource (lib "") (part "CRM1206QFX-1001ELF_1"))
    )
    (comp (ref "R12")
      (value "1K")
      (footprint "SamacSys:RESC3116X65N")
      (description "Resistor")
      (fields
        (field (name "MANUFACTURER_PART_NUMBER") "CRM1206QFX-1001ELF")
        (field (name "MOUSER PART NUMBER") "652-CRM1206QFX-1001E")
      )
      (libsource (lib "SamacSys") (part "CRM1206QFX-1001ELF"))
    )
    (comp (ref "R13")
      (value "1K")
      (footprint "SamacSys:RESC3116X65N")
      (description "1K resistor 1206")
      (fields
        (field (name "MANUFACTURER_PART_NUMBER") "CRM1206QFX-1001ELF")
        (field (name "MOUSER PART NUMBER") "652-CRM1206QFX-1001E")
      )
      (libsource (lib "*") (part "CRM1206QFX-1001ELF"))
    )
    (comp (ref "R15")
      (value "4.7K")
      (footprint "FP-AC1206-MFG")
      (description "AC1206 4.7KΩ 0.25W 1.00%")
      (fields
        (field (name "OCTOPART") "https://octopart.com/ac1206fr-104k7l-yageo-84718857")
        (field (name "TOLERANCE") "0.01")
      )
      (libsource (lib "Altium Content Vault") (part "1029c3af85768c4190bb7ad29bc67b5"))
    )
    (comp (ref "R16")
      (value "4.7K")
      (footprint "FP-AC1206-MFG")
      (description "AC1206 4.7KΩ 0.25W 1.00%")
      (fields
        (field (name "OCTOPART") "https://octopart.com/ac1206fr-104k7l-yageo-84718857")
        (field (name "TOLERANCE") "0.01")
      )
      (libsource (lib "Altium Content Vault") (part "1029c3af85768c4190bb7ad29bc67b5"))
    )
    (comp (ref "R17")
      (value "4.7K")
      (footprint "FP-AC1206-MFG")
      (description "AC1206 4.7KΩ 0.25W 1.00%")
      (fields
        (field (name "OCTOPART") "https://octopart.com/ac1206fr-104k7l-yageo-84718857")
        (field (name "TOLERANCE") "0.01")
      )
      (libsource (lib "Altium Content Vault") (part "1029c3af85768c4190bb7ad29bc67b5"))
    )
    (comp (ref "R18")
      (value "4.7K")
      (footprint "FP-AC1206-MFG")
      (description "AC1206 4.7KΩ 0.25W 1.00%")
      (fields
        (field (name "OCTOPART") "https://octopart.com/ac1206fr-104k7l-yageo-84718857")
        (field (name "TOLERANCE") "0.01")
      )
      (libsource (lib "Altium Content Vault") (part "1029c3af85768c4190bb7ad29bc67b5"))
    )
    (comp (ref "R21")
      (value "300k")
      (footprint "FP-ESR18-IPC_C")
      (description "300kΩ ±1% 0.5W 1206 Anti-Surge Chip Resistor AEC-Q200")
      (fields (field (name "TOLERANCE") "1%"))
      (libsource (lib "Altium Content Vault") (part "1029c3af85768c4190bb7ad29bc67b5"))
    )
    (comp (ref "R22")
      (value "500K")
      (footprint "FP-ESR18-IPC_C")
      (description "300kΩ ±1% 0.5W 1206 Anti-Surge Chip Resistor AEC-Q200")
      (fields (field (name "TOLERANCE") "1%"))
      (libsource (lib "Altium Content Vault") (part "1029c3af85768c4190bb7ad29bc67b5"))
    )
    (comp (ref "R23")
      (value "10K")
      (footprint "FP-ESR18-IPC_C")
      (description "300kΩ ±1% 0.5W 1206 Anti-Surge Chip Resistor AEC-Q200")
      (fields (field (name "TOLERANCE") "1%"))
      (libsource (lib "Altium Content Vault") (part "1029c3af85768c4190bb7ad29bc67b5"))
    )
    (comp (ref "R25")
      (value "AC1206FR-104K7L")
      (footprint "FP-AC1206-MFG")
      (description "AC1206 4.7KΩ 0.25W 1.00%")
      (fields
        (field (name "OCTOPART") "https://octopart.com/ac1206fr-104k7l-yageo-84718857")
        (field (name "TOLERANCE") "0.01")
      )
      (libsource (lib "Altium Content Vault") (part "1029c3af85768c4190bb7ad29bc67b5"))
    )
    (comp (ref "R26")
      (value "AC1206FR-104K7L")
      (footprint "FP-AC1206-MFG")
      (description "AC1206 4.7KΩ 0.25W 1.00%")
      (fields
        (field (name "OCTOPART") "https://octopart.com/ac1206fr-104k7l-yageo-84718857")
        (field (name "TOLERANCE") "0.01")
      )
      (libsource (lib "Altium Content Vault") (part "1029c3af85768c4190bb7ad29bc67b5"))
    )
    (comp (ref "R27")
      (value "AC1206FR-104K7L")
      (footprint "FP-AC1206-MFG")
      (description "AC1206 4.7KΩ 0.25W 1.00%")
      (fields
        (field (name "OCTOPART") "https://octopart.com/ac1206fr-104k7l-yageo-84718857")
        (field (name "TOLERANCE") "0.01")
      )
      (libsource (lib "Altium Content Vault") (part "1029c3af85768c4190bb7ad29bc67b5"))
    )
    (comp (ref "R28")
      (value "AC1206FR-104K7L")
      (footprint "FP-AC1206-MFG")
      (description "AC1206 4.7KΩ 0.25W 1.00%")
      (fields
        (field (name "OCTOPART") "https://octopart.com/ac1206fr-104k7l-yageo-84718857")
        (field (name "TOLERANCE") "0.01")
      )
      (libsource (lib "Altium Content Vault") (part "1029c3af85768c4190bb7ad29bc67b5"))
    )
    (comp (ref "R30")
      (value "300k")
      (footprint "FP-ESR18-IPC_C")
      (description "300kΩ ±1% 0.5W 1206 Anti-Surge Chip Resistor AEC-Q200")
      (fields (field (name "TOLERANCE") "1%"))
      (libsource (lib "Altium Content Vault") (part "1029c3af85768c4190bb7ad29bc67b5"))
    )
    (comp (ref "R31")
      (value "300K")
      (footprint "FP-ESR18-IPC_C")
      (description "300kΩ ±1% 0.5W 1206 Anti-Surge Chip Resistor AEC-Q200")
      (fields (field (name "TOLERANCE") "1%"))
      (libsource (lib "Altium Content Vault") (part "1029c3af85768c4190bb7ad29bc67b5"))
    )
    (comp (ref "R33")
      (value "AC1206FR-104K7L")
      (footprint "FP-AC1206-MFG")
      (description "AC1206 4.7KΩ 0.25W 1.00%")
      (fields
        (field (name "OCTOPART") "https://octopart.com/ac1206fr-104k7l-yageo-84718857")
        (field (name "TOLERANCE") "0.01")
      )
      (libsource (lib "Altium Content Vault") (part "1029c3af85768c4190bb7ad29bc67b5"))
    )
    (comp (ref "R34")
      (value "AC1206FR-104K7L")
      (footprint "FP-AC1206-MFG")
      (description "AC1206 4.7KΩ 0.25W 1.00%")
      (fields
        (field (name "OCTOPART") "https://octopart.com/ac1206fr-104k7l-yageo-84718857")
        (field (name "TOLERANCE") "0.01")
      )
      (libsource (lib "Altium Content Vault") (part "1029c3af85768c4190bb7ad29bc67b5"))
    )
    (comp (ref "R35")
      (value "AC1206FR-104K7L")
      (footprint "FP-AC1206-MFG")
      (description "AC1206 4.7KΩ 0.25W 1.00%")
      (fields
        (field (name "OCTOPART") "https://octopart.com/ac1206fr-104k7l-yageo-84718857")
        (field (name "TOLERANCE") "0.01")
      )
      (libsource (lib "Altium Content Vault") (part "1029c3af85768c4190bb7ad29bc67b5"))
    )
    (comp (ref "R36")
      (value "AC1206FR-104K7L")
      (footprint "FP-AC1206-MFG")
      (description "AC1206 4.7KΩ 0.25W 1.00%")
      (fields
        (field (name "OCTOPART") "https://octopart.com/ac1206fr-104k7l-yageo-84718857")
        (field (name "TOLERANCE") "0.01")
      )
      (libsource (lib "Altium Content Vault") (part "1029c3af85768c4190bb7ad29bc67b5"))
    )
    (comp (ref "R37")
      (value "4.7K")
      (footprint "FP-AC1206-MFG")
      (description "AC1206 4.7KΩ 0.25W 1.00%")
      (fields
        (field (name "OCTOPART") "https://octopart.com/ac1206fr-104k7l-yageo-84718857")
        (field (name "TOLERANCE") "0.01")
      )
      (libsource (lib "Altium Content Vault") (part "1029c3af85768c4190bb7ad29bc67b5"))
    )
    (comp (ref "R38")
      (value "4.7K")
      (footprint "FP-AC1206-MFG")
      (description "AC1206 4.7KΩ 0.25W 1.00%")
      (fields
        (field (name "OCTOPART") "https://octopart.com/ac1206fr-104k7l-yageo-84718857")
        (field (name "TOLERANCE") "0.01")
      )
      (libsource (lib "Altium Content Vault") (part "1029c3af85768c4190bb7ad29bc67b5"))
    )
    (comp (ref "R39")
      (value "4.7K")
      (footprint "FP-AC1206-MFG")
      (description "AC1206 4.7KΩ 0.25W 1.00%")
      (fields
        (field (name "OCTOPART") "https://octopart.com/ac1206fr-104k7l-yageo-84718857")
        (field (name "TOLERANCE") "0.01")
      )
      (libsource (lib "Altium Content Vault") (part "1029c3af85768c4190bb7ad29bc67b5"))
    )
    (comp (ref "R40")
      (value "4.7K")
      (footprint "FP-AC1206-MFG")
      (description "AC1206 4.7KΩ 0.25W 1.00%")
      (fields
        (field (name "OCTOPART") "https://octopart.com/ac1206fr-104k7l-yageo-84718857")
        (field (name "TOLERANCE") "0.01")
      )
      (libsource (lib "Altium Content Vault") (part "1029c3af85768c4190bb7ad29bc67b5"))
    )
    (comp (ref "R41")
      (value "4.7K")
      (footprint "FP-AC1206-MFG")
      (description "AC1206 4.7KΩ 0.25W 1.00%")
      (fields
        (field (name "OCTOPART") "https://octopart.com/ac1206fr-104k7l-yageo-84718857")
        (field (name "TOLERANCE") "0.01")
      )
      (libsource (lib "Altium Content Vault") (part "1029c3af85768c4190bb7ad29bc67b5"))
    )
    (comp (ref "R42")
      (value "4.7K")
      (footprint "FP-AC1206-MFG")
      (description "AC1206 4.7KΩ 0.25W 1.00%")
      (fields
        (field (name "OCTOPART") "https://octopart.com/ac1206fr-104k7l-yageo-84718857")
        (field (name "TOLERANCE") "0.01")
      )
      (libsource (lib "Altium Content Vault") (part "1029c3af85768c4190bb7ad29bc67b5"))
    )
    (comp (ref "R43")
      (value "4.7K")
      (footprint "FP-AC1206-MFG")
      (description "AC1206 4.7KΩ 0.25W 1.00%")
      (fields
        (field (name "OCTOPART") "https://octopart.com/ac1206fr-104k7l-yageo-84718857")
        (field (name "TOLERANCE") "0.01")
      )
      (libsource (lib "Altium Content Vault") (part "1029c3af85768c4190bb7ad29bc67b5"))
    )
    (comp (ref "R44")
      (value "10K")
      (footprint "RESC3116X65X40ML10T20")
      (description "Chip Resistor, 10 KOhm, +/- 1%, 0.25 W, -55 to 155 degC, 1206 (3216 Metric), RoHS, Tape and Reel")
      (fields (field (name "TOLERANCE") "1%") (field (name "MANUFACTURER") "Yageo"))
      (libsource (lib "Altium Content Vault") (part "RES-2"))
    )
    (comp (ref "R45")
      (value "10K")
      (footprint "RESC3116X65X40ML10T20")
      (description "Chip Resistor, 10 KOhm, +/- 1%, 0.25 W, -55 to 155 degC, 1206 (3216 Metric), RoHS, Tape and Reel")
      (fields (field (name "TOLERANCE") "1%") (field (name "MANUFACTURER") "Yageo"))
      (libsource (lib "Altium Content Vault") (part "RES-2"))
    )
    (comp (ref "R46")
      (value "10K")
      (footprint "RESC3116X65X40ML10T20")
      (description "Chip Resistor, 10 KOhm, +/- 1%, 0.25 W, -55 to 155 degC, 1206 (3216 Metric), RoHS, Tape and Reel")
      (fields (field (name "TOLERANCE") "1%") (field (name "MANUFACTURER") "Yageo"))
      (libsource (lib "Altium Content Vault") (part "RES-2"))
    )
    (comp (ref "R47")
      (value "20K")
      (footprint "FP-RT1206-MFG")
      (description "RES SMD 20K OHM 0.25% 1/4W 1206")
      (fields
        (field (name "MANUFACTURER PART NUMBER") "RT1206CRD0720KL")
        (field (name "OCTOPART") "https://octopart.com/rt1206crd0720kl-yageo-1258780")
      )
      (libsource (lib "Altium Content Vault") (part "1029c3af85768c4190bb7ad29bc67b5"))
    )
    (comp (ref "R48")
      (value "20K")
      (footprint "FP-RT1206-MFG")
      (description "RES SMD 20K OHM 0.25% 1/4W 1206")
      (fields
        (field (name "MANUFACTURER PART NUMBER") "RT1206CRD0720KL")
        (field (name "OCTOPART") "https://octopart.com/rt1206crd0720kl-yageo-1258780")
      )
      (libsource (lib "Altium Content Vault") (part "1029c3af85768c4190bb7ad29bc67b5"))
    )
    (comp (ref "R49")
      (value "15K")
      (footprint "FP-ERJ8EN-MFG")
      (fields (field (name "TOLERANCE") "1%"))
      (libsource (lib "Altium Content Vault") (part "1029c3af85768c4190bb7ad29bc67b5"))
    )
    (comp (ref "R51")
      (value "100K")
      (footprint "FP-AC1206-MFG")
      (description "AC1206 4.7KΩ 0.25W 1.00%")
      (fields
        (field (name "OCTOPART") "https://octopart.com/ac1206fr-104k7l-yageo-84718857")
        (field (name "TOLERANCE") "0.01")
      )
      (libsource (lib "Altium Content Vault") (part "1029c3af85768c4190bb7ad29bc67b5"))
    )
    (comp (ref "R52")
      (value "500k")
      (footprint "FP-CRMA1206-IPC_A")
      (description "CRMA1206AF500KFKEF Res Thick Film 1206 500K Ohm 1% 0.3W ±100ppm/C Pad SMD Automotive T/R")
      (fields (field (name "TOLERANCE") "1%"))
      (libsource (lib "Altium Content Vault") (part "1029c3af85768c4190bb7ad29bc67b5"))
    )
    (comp (ref "R53")
      (value "10K")
      (footprint "RESC3116X65X40ML10T20")
      (description "Chip Resistor, 10 KOhm, +/- 1%, 0.25 W, -55 to 155 degC, 1206 (3216 Metric), RoHS, Tape and Reel")
      (fields (field (name "TOLERANCE") "1%") (field (name "MANUFACTURER") "Yageo"))
      (libsource (lib "Altium Content Vault") (part "RES-2"))
    )
    (comp (ref "R54")
      (value "10K")
      (footprint "RESC3116X65X40ML10T20")
      (description "Chip Resistor, 10 KOhm, +/- 1%, 0.25 W, -55 to 155 degC, 1206 (3216 Metric), RoHS, Tape and Reel")
      (fields (field (name "TOLERANCE") "1%") (field (name "MANUFACTURER") "Yageo"))
      (libsource (lib "Altium Content Vault") (part "RES-2"))
    )
    (comp (ref "R55")
      (value "20K")
      (footprint "FP-RT1206-MFG")
      (description "RES SMD 20K OHM 0.25% 1/4W 1206")
      (fields
        (field (name "MANUFACTURER PART NUMBER") "RT1206CRD0720KL")
        (field (name "OCTOPART") "https://octopart.com/rt1206crd0720kl-yageo-1258780")
      )
      (libsource (lib "Altium Content Vault") (part "1029c3af85768c4190bb7ad29bc67b5"))
    )
    (comp (ref "R56")
      (value "10K")
      (footprint "RESC3116X65X40ML10T20")
      (description "Chip Resistor, 10 KOhm, +/- 1%, 0.25 W, -55 to 155 degC, 1206 (3216 Metric), RoHS, Tape and Reel")
      (fields (field (name "TOLERANCE") "1%") (field (name "MANUFACTURER") "Yageo"))
      (libsource (lib "Altium Content Vault") (part "RES-2"))
    )
    (comp (ref "R57")
      (value "20K")
      (footprint "FP-RT1206-MFG")
      (description "RES SMD 20K OHM 0.25% 1/4W 1206")
      (fields
        (field (name "MANUFACTURER PART NUMBER") "RT1206CRD0720KL")
        (field (name "OCTOPART") "https://octopart.com/rt1206crd0720kl-yageo-1258780")
      )
      (libsource (lib "Altium Content Vault") (part "1029c3af85768c4190bb7ad29bc67b5"))
    )
    (comp (ref "R58")
      (value "AC1206FR-10100RL")
      (footprint "SamacSys:RESC3116X65N")
      (description "Resistor")
      (fields (field (name "MOUSER PART NUMBER") "603-AC1206FR-10100RL"))
      (libsource (lib "*") (part "AC1206FR-10100RL"))
    )
    (comp (ref "R59")
      (value "AC1206FR-10100RL")
      (footprint "SamacSys:RESC3116X65N")
      (description "Resistor")
      (fields (field (name "MOUSER PART NUMBER") "603-AC1206FR-10100RL"))
      (libsource (lib "*") (part "AC1206FR-10100RL"))
    )
    (comp (ref "R60")
      (value "1K")
      (footprint "RESC3216X70X50LL05T20")
      (fields (field (name "MANUFACTURER") "Panasonic") (field (name "PART NUMBER") "ERJ-8ENF1001V"))
      (libsource (lib "Altium Content Vault") (part "RES"))
    )
    (comp (ref "R61")
      (value "1K")
      (footprint "RESC3216X70X50LL05T20")
      (fields (field (name "MANUFACTURER") "Panasonic") (field (name "PART NUMBER") "ERJ-8ENF1001V"))
      (libsource (lib "Altium Content Vault") (part "RES"))
    )
    (comp (ref "R62")
      (value "AC1206FR-104K7L")
      (footprint "FP-AC1206-MFG")
      (description "AC1206 4.7KΩ 0.25W 1.00%")
      (fields
        (field (name "OCTOPART") "https://octopart.com/ac1206fr-104k7l-yageo-84718857")
        (field (name "TOLERANCE") "0.01")
      )
      (libsource (lib "Altium Content Vault") (part "1029c3af85768c4190bb7ad29bc67b5"))
    )
    (comp (ref "R63")
      (value "AC1206FR-104K7L")
      (footprint "FP-AC1206-MFG")
      (description "AC1206 4.7KΩ 0.25W 1.00%")
      (fields
        (field (name "OCTOPART") "https://octopart.com/ac1206fr-104k7l-yageo-84718857")
        (field (name "TOLERANCE") "0.01")
      )
      (libsource (lib "Altium Content Vault") (part "1029c3af85768c4190bb7ad29bc67b5"))
    )
    (comp (ref "R64")
      (value "AC1206FR-104K7L")
      (footprint "FP-AC1206-MFG")
      (description "AC1206 4.7KΩ 0.25W 1.00%")
      (fields
        (field (name "OCTOPART") "https://octopart.com/ac1206fr-104k7l-yageo-84718857")
        (field (name "TOLERANCE") "0.01")
      )
      (libsource (lib "Altium Content Vault") (part "1029c3af85768c4190bb7ad29bc67b5"))
    )
    (comp (ref "R65")
      (value "AC1206FR-104K7L")
      (footprint "FP-AC1206-MFG")
      (description "AC1206 4.7KΩ 0.25W 1.00%")
      (fields
        (field (name "OCTOPART") "https://octopart.com/ac1206fr-104k7l-yageo-84718857")
        (field (name "TOLERANCE") "0.01")
      )
      (libsource (lib "Altium Content Vault") (part "1029c3af85768c4190bb7ad29bc67b5"))
    )
    (comp (ref "R68")
      (value "AC1206FR-104K7L")
      (footprint "FP-AC1206-MFG")
      (description "AC1206 4.7KΩ 0.25W 1.00%")
      (fields
        (field (name "OCTOPART") "https://octopart.com/ac1206fr-104k7l-yageo-84718857")
        (field (name "TOLERANCE") "0.01")
      )
      (libsource (lib "Altium Content Vault") (part "1029c3af85768c4190bb7ad29bc67b5"))
    )
    (comp (ref "R69")
      (value "AC1206FR-104K7L")
      (footprint "FP-AC1206-MFG")
      (description "AC1206 4.7KΩ 0.25W 1.00%")
      (fields
        (field (name "OCTOPART") "https://octopart.com/ac1206fr-104k7l-yageo-84718857")
        (field (name "TOLERANCE") "0.01")
      )
      (libsource (lib "Altium Content Vault") (part "1029c3af85768c4190bb7ad29bc67b5"))
    )
    (comp (ref "U1")
      (value "TLV9352IDR")
      (footprint "FP-D0008A-IPC_A")
      (description "IC OPAMP GP 2 CIRCUIT 8SOIC")
      (libsource (lib "Altium Content Vault") (part "d5b36c1049528187b1d2197d5d58d7e"))
    )
    (comp (ref "U2")
      (value "TLV9352IDR")
      (footprint "FP-D0008A-IPC_A")
      (description "IC OPAMP GP 2 CIRCUIT 8SOIC")
      (libsource (lib "Altium Content Vault") (part "d5b36c1049528187b1d2197d5d58d7e"))
    )
    (comp (ref "U3")
      (value "TLV9352IDR")
      (footprint "FP-D0008A-IPC_A")
      (description "IC OPAMP GP 2 CIRCUIT 8SOIC")
      (libsource (lib "Altium Content Vault") (part "d5b36c1049528187b1d2197d5d58d7e"))
    )
    (comp (ref "U4")
      (value "TLV9352IDR")
      (footprint "FP-D0008A-IPC_A")
      (description "IC OPAMP GP 2 CIRCUIT 8SOIC")
      (libsource (lib "Altium Content Vault") (part "d5b36c1049528187b1d2197d5d58d7e"))
    )
    (comp (ref "U5")
      (value "TLV9352IDR")
      (footprint "FP-D0008A-IPC_A")
      (description "IC OPAMP GP 2 CIRCUIT 8SOIC")
      (libsource (lib "Altium Content Vault") (part "d5b36c1049528187b1d2197d5d58d7e"))
    )
    (comp (ref "U6")
      (value "TLV9352IDR")
      (footprint "FP-D0008A-IPC_A")
      (description "IC OPAMP GP 2 CIRCUIT 8SOIC")
      (libsource (lib "Altium Content Vault") (part "d5b36c1049528187b1d2197d5d58d7e"))
    )
    (comp (ref "U7")
      (value "TLV9352IDR")
      (footprint "FP-D0008A-IPC_A")
      (description "IC OPAMP GP 2 CIRCUIT 8SOIC")
      (libsource (lib "Altium Content Vault") (part "d5b36c1049528187b1d2197d5d58d7e"))
    )
    (comp (ref "U8")
      (value "TLV9152IDR")
      (footprint "FP-D0008A-IPC_A")
      (description "IC OPAMP GP 2 CIRCUIT 8SOIC")
      (libsource (lib "Altium Content Vault") (part "d5b36c1049528187b1d2197d5d58d7e"))
    )
    (comp (ref "U9")
      (value "TLV9352IDR")
      (footprint "FP-D0008A-IPC_A")
      (description "IC OPAMP GP 2 CIRCUIT 8SOIC")
      (libsource (lib "Altium Content Vault") (part "d5b36c1049528187b1d2197d5d58d7e"))
    )
    (comp (ref "U10")
      (value "TLV9152IDR")
      (footprint "FP-D0008A-IPC_A")
      (description "IC OPAMP GP 2 CIRCUIT 8SOIC")
      (libsource (lib "Altium Content Vault") (part "d5b36c1049528187b1d2197d5d58d7e"))
    )
    (comp (ref "U11")
      (value "L293DD")
      (footprint "STM-SOIC-20_M")
      (description "Push-Pull Four Channel Driver with Diodes, 4.5 to 36 V, 20-Pin SOIC, RoHS, Tube")
      (fields (field (name "TOLERANCE") "1%"))
      (libsource (lib "Altium Content Vault") (part "STM-L293DD-SO-20"))
    )
    (comp (ref "U12")
      (value "TLV9352IDR")
      (footprint "FP-D0008A-IPC_A")
      (description "IC OPAMP GP 2 CIRCUIT 8SOIC")
      (libsource (lib "Altium Content Vault") (part "d5b36c1049528187b1d2197d5d58d7e"))
    )
    (comp (ref "U13")
      (value "TLV9152IDR")
      (footprint "FP-D0008A-IPC_A")
      (description "IC OPAMP GP 2 CIRCUIT 8SOIC")
      (libsource (lib "Altium Content Vault") (part "d5b36c1049528187b1d2197d5d58d7e"))
    )
    (comp (ref "VR1")
      (value "500")
      (footprint "SamacSys:3296W-1")
      (description "500 Ohm variable Resistor")
      (fields
        (field (name "MANUFACTURER_PART_NUMBER") "3296W-1-101LF")
        (field (name "MOUSER PART NUMBER") "652-3296W-1-101LF")
      )
      (libsource (lib "*") (part "3296W-1-101LF"))
    )
    (comp (ref "VR2")
      (value "3296W-1-102")
      (footprint "SamacSys:3296W-1")
      (description "Variable Resistor")
      (fields (field (name "MOUSER PART NUMBER") "652-3296W-1-102"))
      (libsource (lib "") (part "3296W-1-102_2"))
    )
    (comp (ref "VR3")
      (value "20K")
      (footprint "SamacSys:3296W-1")
      (description "20kOhm Resistor")
      (fields
        (field (name "MANUFACTURER_PART_NUMBER") "3296W-1-203LF")
        (field (name "MOUSER PART NUMBER") "652-3296W-1-203LF")
      )
      (libsource (lib "*") (part "3296W-1-203LF"))
    )
    (comp (ref "VR4")
      (value "20K")
      (footprint "SamacSys:3296W-1")
      (description "20kOhm Resistor")
      (fields
        (field (name "MANUFACTURER_PART_NUMBER") "3296W-1-203LF")
        (field (name "MOUSER PART NUMBER") "652-3296W-1-203LF")
      )
      (libsource (lib "") (part "3296W-1-203LF_2"))
    )
    (comp (ref "VR5")
      (value "100")
      (footprint "SamacSys:3296W-1")
      (description "100 Ohm variable Resistor")
      (fields
        (field (name "MANUFACTURER_PART_NUMBER") "3296W-1-101LF")
        (field (name "MOUSER PART NUMBER") "652-3296W-1-101LF")
      )
      (libsource (lib "*") (part "3296W-1-101LF"))
    )
    (comp (ref "VR6")
      (value "20K")
      (footprint "SamacSys:3296W-1")
      (description "20kOhm Resistor")
      (fields
        (field (name "MANUFACTURER_PART_NUMBER") "3296W-1-203LF")
        (field (name "MOUSER PART NUMBER") "652-3296W-1-203LF")
      )
      (libsource (lib "") (part "3296W-1-203LF_1"))
    )
    (comp (ref "VR7")
      (value "100")
      (footprint "SamacSys:3296W-1")
      (description "100 Ohm variable Resistor")
      (fields
        (field (name "MANUFACTURER_PART_NUMBER") "3296W-1-101LF")
        (field (name "MOUSER PART NUMBER") "652-3296W-1-101LF")
      )
      (libsource (lib "*") (part "3296W-1-101LF"))
    )
    (comp (ref "VR8")
      (value "20K")
      (footprint "SamacSys:3296W-1")
      (description "20kOhm Resistor")
      (fields
        (field (name "MANUFACTURER_PART_NUMBER") "3296W-1-203LF")
        (field (name "MOUSER PART NUMBER") "652-3296W-1-203LF")
      )
      (libsource (lib "") (part "3296W-1-203LF_2"))
    )
    (comp (ref "VR10")
      (value "20K")
      (footprint "SamacSys:3296W-1")
      (description "20kOhm Resistor")
      (fields
        (field (name "MANUFACTURER_PART_NUMBER") "3296W-1-203LF")
        (field (name "MOUSER PART NUMBER") "652-3296W-1-203LF")
      )
      (libsource (lib "") (part "3296W-1-203LF_1"))
    )
    (comp (ref "VR11")
      (value "100")
      (footprint "SamacSys:3296W-1")
      (description "100 Ohm variable Resistor")
      (fields
        (field (name "MANUFACTURER_PART_NUMBER") "3296W-1-101LF")
        (field (name "MOUSER PART NUMBER") "652-3296W-1-101LF")
      )
      (libsource (lib "*") (part "3296W-1-101LF"))
    )
    (comp (ref "VR12")
      (value "6K")
      (footprint "SamacSys:3296W-1")
      (description "6kOhm Resistor")
      (fields
        (field (name "MANUFACTURER_PART_NUMBER") "3296W-1-203LF")
        (field (name "MOUSER PART NUMBER") "652-3296W-1-203LF")
      )
      (libsource (lib "") (part "3296W-1-203LF_1"))
    )
    (comp (ref "VR13")
      (value "3296W-1-102")
      (footprint "SamacSys:3296W-1")
      (description "Variable Resistor")
      (fields (field (name "MOUSER PART NUMBER") "652-3296W-1-102"))
      (libsource (lib "*") (part "3296W-1-102"))
    )
    (comp (ref "VR14")
      (value "3296W-1-102")
      (footprint "SamacSys:3296W-1")
      (description "Variable Resistor")
      (fields (field (name "MOUSER PART NUMBER") "652-3296W-1-102"))
      (libsource (lib "") (part "3296W-1-102_1"))
    )
    (comp (ref "VR15")
      (value "3296W-1-102")
      (footprint "SamacSys:3296W-1")
      (description "Variable Resistor")
      (fields (field (name "MOUSER PART NUMBER") "652-3296W-1-102"))
      (libsource (lib "*") (part "3296W-1-102"))
    )
    (comp (ref "VR16")
      (value "3296W-1-102")
      (footprint "SamacSys:3296W-1")
      (description "Variable Resistor")
      (fields (field (name "MOUSER PART NUMBER") "652-3296W-1-102"))
      (libsource (lib "") (part "3296W-1-102_2"))
    )
  )
  (nets
    (net (code "1") (name "+6V") (class "Default")
      (node (ref "C22") (pin "2") (pinfunction "2_2") (pintype "passive"))
      (node (ref "C24") (pin "2") (pinfunction "2_2") (pintype "passive"))
      (node (ref "C26") (pin "2") (pinfunction "A_2") (pintype "passive"))
      (node (ref "C27") (pin "2") (pinfunction "2_2") (pintype "passive"))
      (node (ref "C32") (pin "2") (pinfunction "A_2") (pintype "passive"))
      (node (ref "IC1") (pin "1") (pinfunction "OUTPUT_1") (pintype "passive"))
      (node (ref "J3") (pin "2") (pinfunction "2_2") (pintype "passive"))
      (node (ref "R16") (pin "2") (pinfunction "2_2") (pintype "passive"))
      (node (ref "R28") (pin "2") (pinfunction "2_2") (pintype "passive"))
      (node (ref "R36") (pin "2") (pinfunction "2_2") (pintype "passive"))
      (node (ref "R68") (pin "1") (pinfunction "1_1") (pintype "passive"))
      (node (ref "R9") (pin "2") (pinfunction "2_2") (pintype "passive"))
      (node (ref "U10") (pin "8") (pinfunction "V+_8") (pintype "power_in"))
      (node (ref "U11") (pin "10") (pinfunction "VS_10") (pintype "power_in"))
      (node (ref "U11") (pin "20") (pinfunction "VSS_20") (pintype "power_in"))
      (node (ref "U8") (pin "8") (pinfunction "V+_8") (pintype "power_in"))
    )
    (net (code "2") (name "+9V") (class "Default")
      (node (ref "C1") (pin "2") (pinfunction "2_2") (pintype "passive"))
      (node (ref "C12") (pin "2") (pinfunction "2_2") (pintype "passive"))
      (node (ref "C15") (pin "2") (pinfunction "2_2") (pintype "passive"))
      (node (ref "C17") (pin "2") (pinfunction "2_2") (pintype "passive"))
      (node (ref "C19") (pin "2") (pinfunction "2_2") (pintype "passive"))
      (node (ref "C3") (pin "2") (pinfunction "2_2") (pintype "passive"))
      (node (ref "C35") (pin "2") (pinfunction "2_2") (pintype "passive"))
      (node (ref "C6") (pin "2") (pinfunction "2_2") (pintype "passive"))
      (node (ref "C8") (pin "2") (pinfunction "2_2") (pintype "passive"))
      (node (ref "J1") (pin "2") (pinfunction "2_2") (pintype "passive"))
      (node (ref "J2") (pin "1") (pinfunction "1_1") (pintype "passive"))
      (node (ref "R43") (pin "2") (pinfunction "2_2") (pintype "passive"))
      (node (ref "U1") (pin "8") (pinfunction "V+_8") (pintype "power_in"))
      (node (ref "U12") (pin "8") (pinfunction "V+_8") (pintype "power_in"))
      (node (ref "U2") (pin "8") (pinfunction "V+_8") (pintype "power_in"))
      (node (ref "U3") (pin "8") (pinfunction "V+_8") (pintype "power_in"))
      (node (ref "U4") (pin "8") (pinfunction "V+_8") (pintype "power_in"))
      (node (ref "U5") (pin "8") (pinfunction "V+_8") (pintype "power_in"))
      (node (ref "U6") (pin "8") (pinfunction "V+_8") (pintype "power_in"))
      (node (ref "U7") (pin "8") (pinfunction "V+_8") (pintype "power_in"))
      (node (ref "U9") (pin "8") (pinfunction "V+_8") (pintype "power_in"))
    )
    (net (code "3") (name "+18") (class "Default")
      (node (ref "C28") (pin "2") (pinfunction "2_2") (pintype "passive"))
      (node (ref "C30") (pin "2") (pinfunction "2_2") (pintype "passive"))
      (node (ref "IC1") (pin "3") (pinfunction "INPUT_3") (pintype "passive"))
      (node (ref "J5") (pin "2") (pinfunction "2_2") (pintype "passive"))
      (node (ref "Q3") (pin "5") (pinfunction "D_1_5") (pintype "passive"))
      (node (ref "Q3") (pin "6") (pinfunction "D_2_6") (pintype "passive"))
      (node (ref "Q3") (pin "7") (pinfunction "D_3_7") (pintype "passive"))
      (node (ref "Q3") (pin "8") (pinfunction "D_4_8") (pintype "passive"))
      (node (ref "Q3") (pin "9") (pinfunction "D_5_9") (pintype "passive"))
      (node (ref "R62") (pin "2") (pinfunction "2_2") (pintype "passive"))
      (node (ref "R64") (pin "2") (pinfunction "2_2") (pintype "passive"))
      (node (ref "U13") (pin "8") (pinfunction "V+_8") (pintype "power_in"))
    )
    (net (code "4") (name "-6V") (class "Default")
      (node (ref "C23") (pin "2") (pinfunction "2_2") (pintype "passive"))
      (node (ref "C25") (pin "2") (pinfunction "2_2") (pintype "passive"))
      (node (ref "C33") (pin "1") (pinfunction "C_1") (pintype "passive"))
      (node (ref "IC2") (pin "2") (pinfunction "OUT_2") (pintype "passive"))
      (node (ref "J3") (pin "1") (pinfunction "1_1") (pintype "passive"))
      (node (ref "R15") (pin "1") (pinfunction "1_1") (pintype "passive"))
      (node (ref "R27") (pin "1") (pinfunction "1_1") (pintype "passive"))
      (node (ref "R35") (pin "1") (pinfunction "1_1") (pintype "passive"))
      (node (ref "R8") (pin "1") (pinfunction "1_1") (pintype "passive"))
      (node (ref "U10") (pin "4") (pinfunction "V-_4") (pintype "power_in"))
      (node (ref "U8") (pin "4") (pinfunction "V-_4") (pintype "power_in"))
    )
    (net (code "5") (name "-9V") (class "Default")
      (node (ref "C13") (pin "2") (pinfunction "2_2") (pintype "passive"))
      (node (ref "C16") (pin "2") (pinfunction "2_2") (pintype "passive"))
      (node (ref "C18") (pin "2") (pinfunction "2_2") (pintype "passive"))
      (node (ref "C2") (pin "2") (pinfunction "2_2") (pintype "passive"))
      (node (ref "C20") (pin "2") (pinfunction "2_2") (pintype "passive"))
      (node (ref "C36") (pin "2") (pinfunction "2_2") (pintype "passive"))
      (node (ref "C7") (pin "2") (pinfunction "2_2") (pintype "passive"))
      (node (ref "C9") (pin "2") (pinfunction "2_2") (pintype "passive"))
      (node (ref "R42") (pin "1") (pinfunction "1_1") (pintype "passive"))
      (node (ref "U1") (pin "4") (pinfunction "V-_4") (pintype "power_in"))
      (node (ref "U12") (pin "4") (pinfunction "V-_4") (pintype "power_in"))
      (node (ref "U2") (pin "4") (pinfunction "V-_4") (pintype "power_in"))
      (node (ref "U3") (pin "4") (pinfunction "V-_4") (pintype "power_in"))
      (node (ref "U4") (pin "4") (pinfunction "V-_4") (pintype "power_in"))
      (node (ref "U5") (pin "4") (pinfunction "V-_4") (pintype "power_in"))
      (node (ref "U6") (pin "4") (pinfunction "V-_4") (pintype "power_in"))
      (node (ref "U7") (pin "4") (pinfunction "V-_4") (pintype "power_in"))
      (node (ref "U9") (pin "4") (pinfunction "V-_4") (pintype "power_in"))
    )
    (net (code "6") (name "-18") (class "Default")
      (node (ref "C28") (pin "1") (pinfunction "1_1") (pintype "passive"))
      (node (ref "C29") (pin "1") (pinfunction "1_1") (pintype "passive"))
      (node (ref "C29") (pin "2") (pinfunction "2_2") (pintype "passive"))
      (node (ref "C31") (pin "1") (pinfunction "1_1") (pintype "passive"))
      (node (ref "IC2") (pin "3") (pinfunction "IN_3") (pintype "passive"))
      (node (ref "J5") (pin "1") (pinfunction "1_1") (pintype "passive"))
      (node (ref "Q4") (pin "5") (pinfunction "D_5") (pintype "passive"))
      (node (ref "R63") (pin "1") (pinfunction "1_1") (pintype "passive"))
      (node (ref "R65") (pin "1") (pinfunction "1_1") (pintype "passive"))
      (node (ref "U13") (pin "4") (pinfunction "V-_4") (pintype "power_in"))
    )
    (net (code "7") (name "/KdOut") (class "Default")
      (node (ref "R39") (pin "1") (pinfunction "1_1") (pintype "passive"))
      (node (ref "U12") (pin "7") (pinfunction "OUT2_7") (pintype "passive"))
      (node (ref "VR10") (pin "2") (pinfunction "WIPER_2") (pintype "passive"))
    )
    (net (code "8") (name "/KiOut") (class "Default")
      (node (ref "R38") (pin "1") (pinfunction "1_1") (pintype "passive"))
      (node (ref "U4") (pin "7") (pinfunction "OUT2_7") (pintype "passive"))
      (node (ref "VR16") (pin "2") (pinfunction "WIPER_2") (pintype "passive"))
    )
    (net (code "9") (name "/KpOut") (class "Default")
      (node (ref "R37") (pin "1") (pinfunction "1_1") (pintype "passive"))
      (node (ref "U3") (pin "7") (pinfunction "OUT2_7") (pintype "passive"))
      (node (ref "VR6") (pin "2") (pinfunction "WIPER_2") (pintype "passive"))
    )
    (net (code "10") (name "/PIDOut") (class "Default")
      (node (ref "R40") (pin "1") (pinfunction "1_1") (pintype "passive"))
      (node (ref "R44") (pin "1") (pinfunction "1_1") (pintype "passive"))
      (node (ref "R47") (pin "1") (pinfunction "1_1") (pintype "passive"))
      (node (ref "U10") (pin "3") (pinfunction "IN1+_3") (pintype "tri_state"))
      (node (ref "U10") (pin "6") (pinfunction "IN2-_6") (pintype "tri_state"))
      (node (ref "U5") (pin "1") (pinfunction "OUT1_1") (pintype "passive"))
    )
    (net (code "11") (name "/SensorError") (class "Default")
      (node (ref "C11") (pin "1") (pinfunction "1_1") (pintype "passive"))
      (node (ref "R11") (pin "2") (pinfunction "2_2") (pintype "passive"))
      (node (ref "R23") (pin "1") (pinfunction "1_1") (pintype "passive"))
      (node (ref "U2") (pin "7") (pinfunction "OUT2_7") (pintype "passive"))
      (node (ref "VR2") (pin "2") (pinfunction "WIPER_2") (pintype "passive"))
    )
    (net (code "12") (name "GND") (class "Default")
      (node (ref "C1") (pin "1") (pinfunction "1_1") (pintype "passive"))
      (node (ref "C12") (pin "1") (pinfunction "1_1") (pintype "passive"))
      (node (ref "C13") (pin "1") (pinfunction "1_1") (pintype "passive"))
      (node (ref "C15") (pin "1") (pinfunction "1_1") (pintype "passive"))
      (node (ref "C16") (pin "1") (pinfunction "1_1") (pintype "passive"))
      (node (ref "C17") (pin "1") (pinfunction "1_1") (pintype "passive"))
      (node (ref "C18") (pin "1") (pinfunction "1_1") (pintype "passive"))
      (node (ref "C19") (pin "1") (pinfunction "1_1") (pintype "passive"))
      (node (ref "C2") (pin "1") (pinfunction "1_1") (pintype "passive"))
      (node (ref "C20") (pin "1") (pinfunction "1_1") (pintype "passive"))
      (node (ref "C22") (pin "1") (pinfunction "1_1") (pintype "passive"))
      (node (ref "C23") (pin "1") (pinfunction "1_1") (pintype "passive"))
      (node (ref "C24") (pin "1") (pinfunction "1_1") (pintype "passive"))
      (node (ref "C25") (pin "1") (pinfunction "1_1") (pintype "passive"))
      (node (ref "C26") (pin "1") (pinfunction "C_1") (pintype "passive"))
      (node (ref "C27") (pin "1") (pinfunction "1_1") (pintype "passive"))
      (node (ref "C3") (pin "1") (pinfunction "1_1") (pintype "passive"))
      (node (ref "C30") (pin "1") (pinfunction "1_1") (pintype "passive"))
      (node (ref "C31") (pin "2") (pinfunction "2_2") (pintype "passive"))
      (node (ref "C32") (pin "1") (pinfunction "C_1") (pintype "passive"))
      (node (ref "C33") (pin "2") (pinfunction "A_2") (pintype "passive"))
      (node (ref "C34") (pin "2") (pinfunction "2_2") (pintype "passive"))
      (node (ref "C35") (pin "1") (pinfunction "1_1") (pintype "passive"))
      (node (ref "C36") (pin "1") (pinfunction "1_1") (pintype "passive"))
      (node (ref "C6") (pin "1") (pinfunction "1_1") (pintype "passive"))
      (node (ref "C7") (pin "1") (pinfunction "1_1") (pintype "passive"))
      (node (ref "C8") (pin "1") (pinfunction "1_1") (pintype "passive"))
      (node (ref "C9") (pin "1") (pinfunction "1_1") (pintype "passive"))
      (node (ref "IC1") (pin "2") (pinfunction "GND_2") (pintype "passive"))
      (node (ref "IC2") (pin "1") (pinfunction "GND_1") (pintype "passive"))
      (node (ref "J3") (pin "3") (pinfunction "3_3") (pintype "passive"))
      (node (ref "Q1") (pin "2") (pinfunction "E_2") (pintype "passive"))
      (node (ref "Q2") (pin "2") (pinfunction "E_2") (pintype "passive"))
      (node (ref "Q3") (pin "1") (pinfunction "S_1_1") (pintype "passive"))
      (node (ref "Q3") (pin "2") (pinfunction "S_2_2") (pintype "passive"))
      (node (ref "Q3") (pin "3") (pinfunction "S_3_3") (pintype "passive"))
      (node (ref "Q4") (pin "1") (pinfunction "S_1") (pintype "passive"))
      (node (ref "Q4") (pin "2") (pinfunction "S_2") (pintype "passive"))
      (node (ref "Q4") (pin "3") (pinfunction "S_3") (pintype "passive"))
      (node (ref "R1") (pin "1") (pinfunction "1_1") (pintype "passive"))
      (node (ref "R10") (pin "2") (pinfunction "2_2") (pintype "passive"))
      (node (ref "R12") (pin "2") (pinfunction "2_2") (pintype "passive"))
      (node (ref "R18") (pin "1") (pinfunction "1_1") (pintype "passive"))
      (node (ref "R2") (pin "1") (pinfunction "1_1") (pintype "passive"))
      (node (ref "R21") (pin "2") (pinfunction "2_2") (pintype "passive"))
      (node (ref "R26") (pin "1") (pinfunction "1_1") (pintype "passive"))
      (node (ref "R30") (pin "2") (pinfunction "2_2") (pintype "passive"))
      (node (ref "R34") (pin "2") (pinfunction "2_2") (pintype "passive"))
      (node (ref "R41") (pin "1") (pinfunction "1_1") (pintype "passive"))
      (node (ref "R5") (pin "1") (pinfunction "1_1") (pintype "passive"))
      (node (ref "R51") (pin "2") (pinfunction "2_2") (pintype "passive"))
      (node (ref "R69") (pin "1") (pinfunction "1_1") (pintype "passive"))
      (node (ref "U10") (pin "2") (pinfunction "IN1-_2") (pintype "tri_state"))
      (node (ref "U10") (pin "5") (pinfunction "IN2+_5") (pintype "tri_state"))
      (node (ref "U11") (pin "14") (pinfunction "GND_14") (pintype "power_in"))
      (node (ref "U11") (pin "15") (pinfunction "GND_15") (pintype "power_in"))
      (node (ref "U11") (pin "16") (pinfunction "GND_16") (pintype "power_in"))
      (node (ref "U11") (pin "17") (pinfunction "GND_17") (pintype "power_in"))
      (node (ref "U11") (pin "4") (pinfunction "GND_4") (pintype "power_in"))
      (node (ref "U11") (pin "5") (pinfunction "GND_5") (pintype "power_in"))
      (node (ref "U11") (pin "6") (pinfunction "GND_6") (pintype "power_in"))
      (node (ref "U11") (pin "7") (pinfunction "GND_7") (pintype "power_in"))
      (node (ref "U13") (pin "2") (pinfunction "IN1-_2") (pintype "tri_state"))
      (node (ref "U6") (pin "3") (pinfunction "IN1+_3") (pintype "tri_state"))
      (node (ref "U6") (pin "5") (pinfunction "IN2+_5") (pintype "tri_state"))
      (node (ref "U7") (pin "3") (pinfunction "IN1+_3") (pintype "tri_state"))
      (node (ref "U7") (pin "5") (pinfunction "IN2+_5") (pintype "tri_state"))
      (node (ref "U8") (pin "3") (pinfunction "IN1+_3") (pintype "tri_state"))
      (node (ref "U8") (pin "5") (pinfunction "IN2+_5") (pintype "tri_state"))
      (node (ref "VR13") (pin "3") (pinfunction "CW_3") (pintype "passive"))
      (node (ref "VR14") (pin "1") (pinfunction "CCW_1") (pintype "passive"))
      (node (ref "VR3") (pin "3") (pinfunction "CW_3") (pintype "passive"))
      (node (ref "VR4") (pin "2") (pinfunction "WIPER_2") (pintype "passive"))
      (node (ref "VR8") (pin "2") (pinfunction "WIPER_2") (pintype "passive"))
    )
    (net (code "13") (name "Net-(D1-A)") (class "Default")
      (node (ref "D1") (pin "2") (pinfunction "A_2") (pintype "passive"))
      (node (ref "R45") (pin "2") (pinfunction "2_2") (pintype "passive"))
      (node (ref "R46") (pin "1") (pinfunction "1_1") (pintype "passive"))
    )
    (net (code "14") (name "Net-(D1-K)") (class "Default")
      (node (ref "D1") (pin "1") (pinfunction "K_1") (pintype "passive"))
      (node (ref "D2") (pin "2") (pinfunction "A_2") (pintype "passive"))
      (node (ref "U7") (pin "1") (pinfunction "OUT1_1") (pintype "passive"))
    )
    (net (code "15") (name "Net-(D2-K)") (class "Default")
      (node (ref "D2") (pin "1") (pinfunction "K_1") (pintype "passive"))
      (node (ref "R44") (pin "2") (pinfunction "2_2") (pintype "passive"))
      (node (ref "R45") (pin "1") (pinfunction "1_1") (pintype "passive"))
      (node (ref "U7") (pin "2") (pinfunction "IN1-_2") (pintype "tri_state"))
    )
    (net (code "16") (name "Net-(D3-A)") (class "Default")
      (node (ref "D3") (pin "2") (pinfunction "A_2") (pintype "passive"))
      (node (ref "R54") (pin "2") (pinfunction "2_2") (pintype "passive"))
      (node (ref "R56") (pin "1") (pinfunction "1_1") (pintype "passive"))
    )
    (net (code "17") (name "Net-(D3-K)") (class "Default")
      (node (ref "D3") (pin "1") (pinfunction "K_1") (pintype "passive"))
      (node (ref "D4") (pin "2") (pinfunction "A_2") (pintype "passive"))
      (node (ref "U8") (pin "1") (pinfunction "OUT1_1") (pintype "passive"))
    )
    (net (code "18") (name "Net-(D4-K)") (class "Default")
      (node (ref "D4") (pin "1") (pinfunction "K_1") (pintype "passive"))
      (node (ref "R53") (pin "2") (pinfunction "2_2") (pintype "passive"))
      (node (ref "R54") (pin "1") (pinfunction "1_1") (pintype "passive"))
      (node (ref "U8") (pin "2") (pinfunction "IN1-_2") (pintype "tri_state"))
    )
    (net (code "19") (name "Net-(D5-A)") (class "Default")
      (node (ref "D5") (pin "2") (pinfunction "A_2") (pintype "passive"))
      (node (ref "Q3") (pin "4") (pinfunction "G_4") (pintype "passive"))
      (node (ref "R64") (pin "1") (pinfunction "1_1") (pintype "passive"))
    )
    (net (code "20") (name "Net-(D5-K)") (class "Default")
      (node (ref "D5") (pin "1") (pinfunction "K_1") (pintype "passive"))
      (node (ref "D6") (pin "2") (pinfunction "A_2") (pintype "passive"))
    )
    (net (code "21") (name "Net-(D6-K)") (class "Default")
      (node (ref "D6") (pin "1") (pinfunction "K_1") (pintype "passive"))
      (node (ref "D7") (pin "2") (pinfunction "A_2") (pintype "passive"))
    )
    (net (code "22") (name "Net-(D7-K)") (class "Default")
      (node (ref "D7") (pin "1") (pinfunction "K_1") (pintype "passive"))
      (node (ref "D8") (pin "2") (pinfunction "A_2") (pintype "passive"))
      (node (ref "U13") (pin "1") (pinfunction "OUT1_1") (pintype "passive"))
    )
    (net (code "23") (name "Net-(D8-K)") (class "Default")
      (node (ref "D8") (pin "1") (pinfunction "K_1") (pintype "passive"))
      (node (ref "D9") (pin "2") (pinfunction "A_2") (pintype "passive"))
    )
    (net (code "24") (name "Net-(D10-A)") (class "Default")
      (node (ref "D10") (pin "2") (pinfunction "A_2") (pintype "passive"))
      (node (ref "D9") (pin "1") (pinfunction "K_1") (pintype "passive"))
    )
    (net (code "25") (name "Net-(D10-K)") (class "Default")
      (node (ref "D10") (pin "1") (pinfunction "K_1") (pintype "passive"))
      (node (ref "Q4") (pin "4") (pinfunction "G_4") (pintype "passive"))
      (node (ref "R65") (pin "2") (pinfunction "2_2") (pintype "passive"))
    )
    (net (code "26") (name "Net-(Q1-B)") (class "Default")
      (node (ref "Q1") (pin "1") (pinfunction "B_1") (pintype "passive"))
      (node (ref "R60") (pin "2") (pinfunction "2_2") (pintype "passive"))
    )
    (net (code "27") (name "Net-(Q1-C_1)") (class "Default")
      (node (ref "Q1") (pin "3") (pinfunction "C_1_3") (pintype "passive"))
      (node (ref "Q1") (pin "4") (pinfunction "C_2_4") (pintype "passive"))
    )
    (net (code "28") (name "Net-(Q2-B)") (class "Default")
      (node (ref "Q2") (pin "1") (pinfunction "B_1") (pintype "passive"))
      (node (ref "R61") (pin "2") (pinfunction "2_2") (pintype "passive"))
    )
    (net (code "29") (name "Net-(Q2-C_1)") (class "Default")
      (node (ref "Q2") (pin "3") (pinfunction "C_1_3") (pintype "passive"))
      (node (ref "Q2") (pin "4") (pinfunction "C_2_4") (pintype "passive"))
      (node (ref "R59") (pin "2") (pinfunction "2_2") (pintype "passive"))
      (node (ref "U11") (pin "9") (pinfunction "INPUT2_9") (pintype "input"))
    )
    (net (code "30") (name "Net-(R8-Pad2)") (class "Default")
      (node (ref "R8") (pin "2") (pinfunction "2_2") (pintype "passive"))
      (node (ref "VR1") (pin "1") (pinfunction "1_1") (pintype "passive"))
    )
    (net (code "31") (name "Net-(R9-Pad1)") (class "Default")
      (node (ref "R9") (pin "1") (pinfunction "1_1") (pintype "passive"))
      (node (ref "VR1") (pin "3") (pinfunction "3_3") (pintype "passive"))
    )
    (net (code "32") (name "Net-(R15-Pad2)") (class "Default")
      (node (ref "R15") (pin "2") (pinfunction "2_2") (pintype "passive"))
      (node (ref "VR5") (pin "1") (pinfunction "1_1") (pintype "passive"))
    )
    (net (code "33") (name "Net-(R16-Pad1)") (class "Default")
      (node (ref "R16") (pin "1") (pinfunction "1_1") (pintype "passive"))
      (node (ref "VR5") (pin "3") (pinfunction "3_3") (pintype "passive"))
    )
    (net (code "34") (name "Net-(R35-Pad2)") (class "Default")
      (node (ref "R35") (pin "2") (pinfunction "2_2") (pintype "passive"))
      (node (ref "VR7") (pin "1") (pinfunction "1_1") (pintype "passive"))
    )
    (net (code "35") (name "Net-(R36-Pad1)") (class "Default")
      (node (ref "R36") (pin "1") (pinfunction "1_1") (pintype "passive"))
      (node (ref "VR7") (pin "3") (pinfunction "3_3") (pintype "passive"))
    )
    (net (code "36") (name "Net-(R42-Pad2)") (class "Default")
      (node (ref "R42") (pin "2") (pinfunction "2_2") (pintype "passive"))
      (node (ref "VR11") (pin "1") (pinfunction "1_1") (pintype "passive"))
    )
    (net (code "37") (name "Net-(R43-Pad1)") (class "Default")
      (node (ref "R43") (pin "1") (pinfunction "1_1") (pintype "passive"))
      (node (ref "VR11") (pin "3") (pinfunction "3_3") (pintype "passive"))
    )
    (net (code "38") (name "Net-(U1A-IN1+)") (class "Default")
      (node (ref "J2") (pin "2") (pinfunction "2_2") (pintype "passive"))
      (node (ref "R2") (pin "2") (pinfunction "2_2") (pintype "passive"))
      (node (ref "U1") (pin "3") (pinfunction "IN1+_3") (pintype "tri_state"))
    )
    (net (code "39") (name "Net-(U1A-IN1-)") (class "Default")
      (node (ref "R3") (pin "1") (pinfunction "1_1") (pintype "passive"))
      (node (ref "U1") (pin "1") (pinfunction "OUT1_1") (pintype "passive"))
      (node (ref "U1") (pin "2") (pinfunction "IN1-_2") (pintype "tri_state"))
    )
    (net (code "40") (name "Net-(U1B-IN2+)") (class "Default")
      (node (ref "J1") (pin "1") (pinfunction "1_1") (pintype "passive"))
      (node (ref "R1") (pin "2") (pinfunction "2_2") (pintype "passive"))
      (node (ref "U1") (pin "5") (pinfunction "IN2+_5") (pintype "tri_state"))
    )
    (net (code "41") (name "Net-(U1B-IN2-)") (class "Default")
      (node (ref "R4") (pin "1") (pinfunction "1_1") (pintype "passive"))
      (node (ref "U1") (pin "6") (pinfunction "IN2-_6") (pintype "tri_state"))
      (node (ref "U1") (pin "7") (pinfunction "OUT2_7") (pintype "passive"))
    )
    (net (code "42") (name "Net-(U2A-IN1+)") (class "Default")
      (node (ref "R4") (pin "2") (pinfunction "2_2") (pintype "passive"))
      (node (ref "R5") (pin "2") (pinfunction "2_2") (pintype "passive"))
      (node (ref "U2") (pin "3") (pinfunction "IN1+_3") (pintype "tri_state"))
    )
    (net (code "43") (name "Net-(U2A-IN1-)") (class "Default")
      (node (ref "R3") (pin "2") (pinfunction "2_2") (pintype "passive"))
      (node (ref "R6") (pin "1") (pinfunction "1_1") (pintype "passive"))
      (node (ref "U2") (pin "2") (pinfunction "IN1-_2") (pintype "tri_state"))
    )
    (net (code "44") (name "Net-(U2A-OUT1)") (class "Default")
      (node (ref "R6") (pin "2") (pinfunction "2_2") (pintype "passive"))
      (node (ref "R7") (pin "1") (pinfunction "1_1") (pintype "passive"))
      (node (ref "U2") (pin "1") (pinfunction "OUT1_1") (pintype "passive"))
    )
    (net (code "45") (name "Net-(U2B-IN2+)") (class "Default")
      (node (ref "R10") (pin "1") (pinfunction "1_1") (pintype "passive"))
      (node (ref "U2") (pin "5") (pinfunction "IN2+_5") (pintype "tri_state"))
      (node (ref "VR1") (pin "2") (pinfunction "2_2") (pintype "passive"))
      (node (ref "VR3") (pin "2") (pinfunction "WIPER_2") (pintype "passive"))
    )
    (net (code "46") (name "Net-(U2B-IN2-)") (class "Default")
      (node (ref "R7") (pin "2") (pinfunction "2_2") (pintype "passive"))
      (node (ref "U2") (pin "6") (pinfunction "IN2-_6") (pintype "tri_state"))
      (node (ref "VR2") (pin "3") (pinfunction "CW_3") (pintype "passive"))
    )
    (net (code "47") (name "Net-(U3A-IN1+)") (class "Default")
      (node (ref "R12") (pin "1") (pinfunction "1_1") (pintype "passive"))
      (node (ref "U3") (pin "3") (pinfunction "IN1+_3") (pintype "tri_state"))
    )
    (net (code "48") (name "Net-(U3A-IN1-)") (class "Default")
      (node (ref "R11") (pin "1") (pinfunction "1_1") (pintype "passive"))
      (node (ref "R13") (pin "1") (pinfunction "1_1") (pintype "passive"))
      (node (ref "U3") (pin "2") (pinfunction "IN1-_2") (pintype "tri_state"))
    )
    (net (code "49") (name "Net-(U3A-OUT1)") (class "Default")
      (node (ref "R13") (pin "2") (pinfunction "2_2") (pintype "passive"))
      (node (ref "R17") (pin "2") (pinfunction "2_2") (pintype "passive"))
      (node (ref "U3") (pin "1") (pinfunction "OUT1_1") (pintype "passive"))
    )
    (net (code "50") (name "Net-(U3B-IN2+)") (class "Default")
      (node (ref "R18") (pin "2") (pinfunction "2_2") (pintype "passive"))
      (node (ref "U3") (pin "5") (pinfunction "IN2+_5") (pintype "tri_state"))
      (node (ref "VR4") (pin "3") (pinfunction "CW_3") (pintype "passive"))
      (node (ref "VR5") (pin "2") (pinfunction "2_2") (pintype "passive"))
    )
    (net (code "51") (name "Net-(U3B-IN2-)") (class "Default")
      (node (ref "R17") (pin "1") (pinfunction "1_1") (pintype "passive"))
      (node (ref "U3") (pin "6") (pinfunction "IN2-_6") (pintype "tri_state"))
      (node (ref "VR6") (pin "3") (pinfunction "CW_3") (pintype "passive"))
    )
    (net (code "52") (name "Net-(U4A-IN1+)") (class "Default")
      (node (ref "R21") (pin "1") (pinfunction "1_1") (pintype "passive"))
      (node (ref "U4") (pin "3") (pinfunction "IN1+_3") (pintype "tri_state"))
    )
    (net (code "53") (name "Net-(U4A-IN1-)") (class "Default")
      (node (ref "C10") (pin "1") (pinfunction "1_1") (pintype "passive"))
      (node (ref "R22") (pin "1") (pinfunction "1_1") (pintype "passive"))
      (node (ref "R23") (pin "2") (pinfunction "2_2") (pintype "passive"))
      (node (ref "U4") (pin "2") (pinfunction "IN1-_2") (pintype "tri_state"))
    )
    (net (code "54") (name "Net-(U4A-OUT1)") (class "Default")
      (node (ref "C10") (pin "2") (pinfunction "2_2") (pintype "passive"))
      (node (ref "R22") (pin "2") (pinfunction "2_2") (pintype "passive"))
      (node (ref "R25") (pin "1") (pinfunction "1_1") (pintype "passive"))
      (node (ref "U4") (pin "1") (pinfunction "OUT1_1") (pintype "passive"))
    )
    (net (code "55") (name "Net-(U4B-IN2+)") (class "Default")
      (node (ref "R26") (pin "2") (pinfunction "2_2") (pintype "passive"))
      (node (ref "U4") (pin "5") (pinfunction "IN2+_5") (pintype "tri_state"))
      (node (ref "VR14") (pin "2") (pinfunction "WIPER_2") (pintype "passive"))
      (node (ref "VR15") (pin "2") (pinfunction "WIPER_2") (pintype "passive"))
    )
    (net (code "56") (name "Net-(U4B-IN2-)") (class "Default")
      (node (ref "R25") (pin "2") (pinfunction "2_2") (pintype "passive"))
      (node (ref "U4") (pin "6") (pinfunction "IN2-_6") (pintype "tri_state"))
      (node (ref "VR16") (pin "3") (pinfunction "CW_3") (pintype "passive"))
    )
    (net (code "57") (name "Net-(U5A-IN1+)") (class "Default")
      (node (ref "R41") (pin "2") (pinfunction "2_2") (pintype "passive"))
      (node (ref "U5") (pin "3") (pinfunction "IN1+_3") (pintype "tri_state"))
      (node (ref "VR11") (pin "2") (pinfunction "2_2") (pintype "passive"))
    )
    (net (code "58") (name "Net-(U5A-IN1-)") (class "Default")
      (node (ref "R37") (pin "2") (pinfunction "2_2") (pintype "passive"))
      (node (ref "R38") (pin "2") (pinfunction "2_2") (pintype "passive"))
      (node (ref "R39") (pin "2") (pinfunction "2_2") (pintype "passive"))
      (node (ref "R40") (pin "2") (pinfunction "2_2") (pintype "passive"))
      (node (ref "U5") (pin "2") (pinfunction "IN1-_2") (pintype "tri_state"))
    )
    (net (code "59") (name "Net-(U6A-IN1-)") (class "Default")
      (node (ref "C34") (pin "1") (pinfunction "1_1") (pintype "passive"))
      (node (ref "R49") (pin "1") (pinfunction "1_1") (pintype "passive"))
      (node (ref "U6") (pin "2") (pinfunction "IN1-_2") (pintype "tri_state"))
    )
    (net (code "60") (name "Net-(U6A-OUT1)") (class "Default")
      (node (ref "R49") (pin "2") (pinfunction "2_2") (pintype "passive"))
      (node (ref "R51") (pin "1") (pinfunction "1_1") (pintype "passive"))
      (node (ref "U6") (pin "1") (pinfunction "OUT1_1") (pintype "passive"))
      (node (ref "VR12") (pin "2") (pinfunction "WIPER_2") (pintype "passive"))
    )
    (net (code "61") (name "Net-(U6B-IN2-)") (class "Default")
      (node (ref "C21") (pin "1") (pinfunction "1_1") (pintype "passive"))
      (node (ref "R52") (pin "2") (pinfunction "2_2") (pintype "passive"))
      (node (ref "U6") (pin "6") (pinfunction "IN2-_6") (pintype "tri_state"))
      (node (ref "VR12") (pin "1") (pinfunction "CCW_1") (pintype "passive"))
    )
    (net (code "62") (name "Net-(U6B-OUT2)") (class "Default")
      (node (ref "C21") (pin "2") (pinfunction "2_2") (pintype "passive"))
      (node (ref "R52") (pin "1") (pinfunction "1_1") (pintype "passive"))
      (node (ref "R53") (pin "1") (pinfunction "1_1") (pintype "passive"))
      (node (ref "R55") (pin "1") (pinfunction "1_1") (pintype "passive"))
      (node (ref "U6") (pin "7") (pinfunction "OUT2_7") (pintype "passive"))
    )
    (net (code "63") (name "Net-(U7B-IN2-)") (class "Default")
      (node (ref "R46") (pin "2") (pinfunction "2_2") (pintype "passive"))
      (node (ref "R47") (pin "2") (pinfunction "2_2") (pintype "passive"))
      (node (ref "R48") (pin "1") (pinfunction "1_1") (pintype "passive"))
      (node (ref "U7") (pin "6") (pinfunction "IN2-_6") (pintype "tri_state"))
    )
    (net (code "64") (name "Net-(U7B-OUT2)") (class "Default")
      (node (ref "R48") (pin "2") (pinfunction "2_2") (pintype "passive"))
      (node (ref "U7") (pin "7") (pinfunction "OUT2_7") (pintype "passive"))
      (node (ref "U9") (pin "3") (pinfunction "IN1+_3") (pintype "tri_state"))
    )
    (net (code "65") (name "Net-(U8B-IN2-)") (class "Default")
      (node (ref "R55") (pin "2") (pinfunction "2_2") (pintype "passive"))
      (node (ref "R56") (pin "2") (pinfunction "2_2") (pintype "passive"))
      (node (ref "R57") (pin "1") (pinfunction "1_1") (pintype "passive"))
      (node (ref "U8") (pin "6") (pinfunction "IN2-_6") (pintype "tri_state"))
    )
    (net (code "66") (name "Net-(U8B-OUT2)") (class "Default")
      (node (ref "R57") (pin "2") (pinfunction "2_2") (pintype "passive"))
      (node (ref "U8") (pin "7") (pinfunction "OUT2_7") (pintype "passive"))
      (node (ref "U9") (pin "2") (pinfunction "IN1-_2") (pintype "tri_state"))
    )
    (net (code "67") (name "Net-(U9A-OUT1)") (class "Default")
      (node (ref "U9") (pin "1") (pinfunction "OUT1_1") (pintype "passive"))
      (node (ref "VR13") (pin "1") (pinfunction "CCW_1") (pintype "passive"))
    )
    (net (code "68") (name "Net-(U10A-OUT1)") (class "Default")
      (node (ref "R60") (pin "1") (pinfunction "1_1") (pintype "passive"))
      (node (ref "U10") (pin "1") (pinfunction "OUT1_1") (pintype "passive"))
    )
    (net (code "69") (name "Net-(U10B-OUT2)") (class "Default")
      (node (ref "R61") (pin "1") (pinfunction "1_1") (pintype "passive"))
      (node (ref "U10") (pin "7") (pinfunction "OUT2_7") (pintype "passive"))
    )
    (net (code "70") (name "Net-(U11-ENABLE1)") (class "Default")
      (node (ref "R68") (pin "2") (pinfunction "2_2") (pintype "passive"))
      (node (ref "R69") (pin "2") (pinfunction "2_2") (pintype "passive"))
      (node (ref "U11") (pin "1") (pinfunction "ENABLE1_1") (pintype "input"))
    )
    (net (code "71") (name "Net-(U11-OUTPUT1)") (class "Default")
      (node (ref "J4") (pin "1") (pinfunction "1_1") (pintype "passive"))
      (node (ref "U11") (pin "3") (pinfunction "OUTPUT1_3") (pintype "output"))
    )
    (net (code "72") (name "Net-(U11-OUTPUT2)") (class "Default")
      (node (ref "J4") (pin "2") (pinfunction "2_2") (pintype "passive"))
      (node (ref "U11") (pin "8") (pinfunction "OUTPUT2_8") (pintype "output"))
    )
    (net (code "73") (name "Net-(U12A-IN1+)") (class "Default")
      (node (ref "R30") (pin "1") (pinfunction "1_1") (pintype "passive"))
      (node (ref "U12") (pin "3") (pinfunction "IN1+_3") (pintype "tri_state"))
    )
    (net (code "74") (name "Net-(U12A-IN1-)") (class "Default")
      (node (ref "C11") (pin "2") (pinfunction "2_2") (pintype "passive"))
      (node (ref "C14") (pin "1") (pinfunction "1_1") (pintype "passive"))
      (node (ref "R31") (pin "1") (pinfunction "1_1") (pintype "passive"))
      (node (ref "U12") (pin "2") (pinfunction "IN1-_2") (pintype "tri_state"))
    )
    (net (code "75") (name "Net-(U12A-OUT1)") (class "Default")
      (node (ref "C14") (pin "2") (pinfunction "2_2") (pintype "passive"))
      (node (ref "R31") (pin "2") (pinfunction "2_2") (pintype "passive"))
      (node (ref "R33") (pin "1") (pinfunction "1_1") (pintype "passive"))
      (node (ref "U12") (pin "1") (pinfunction "OUT1_1") (pintype "passive"))
    )
    (net (code "76") (name "Net-(U12B-IN2+)") (class "Default")
      (node (ref "R34") (pin "1") (pinfunction "1_1") (pintype "passive"))
      (node (ref "U12") (pin "5") (pinfunction "IN2+_5") (pintype "tri_state"))
      (node (ref "VR7") (pin "2") (pinfunction "2_2") (pintype "passive"))
      (node (ref "VR8") (pin "3") (pinfunction "CW_3") (pintype "passive"))
    )
    (net (code "77") (name "Net-(U12B-IN2-)") (class "Default")
      (node (ref "R33") (pin "2") (pinfunction "2_2") (pintype "passive"))
      (node (ref "U12") (pin "6") (pinfunction "IN2-_6") (pintype "tri_state"))
      (node (ref "VR10") (pin "3") (pinfunction "CW_3") (pintype "passive"))
    )
    (net (code "78") (name "Net-(U13A-IN1+)") (class "Default")
      (node (ref "R62") (pin "1") (pinfunction "1_1") (pintype "passive"))
      (node (ref "R63") (pin "2") (pinfunction "2_2") (pintype "passive"))
      (node (ref "U13") (pin "3") (pinfunction "IN1+_3") (pintype "tri_state"))
    )
    (net (code "79") (name "Net-(VR13-WIPER)") (class "Default")
      (node (ref "R58") (pin "1") (pinfunction "1_1") (pintype "passive"))
      (node (ref "R59") (pin "1") (pinfunction "1_1") (pintype "passive"))
      (node (ref "VR13") (pin "2") (pinfunction "WIPER_2") (pintype "passive"))
    )
    (net (code "80") (name "Net-(VR15-CCW)") (class "Default")
      (node (ref "R27") (pin "2") (pinfunction "2_2") (pintype "passive"))
      (node (ref "VR15") (pin "1") (pinfunction "CCW_1") (pintype "passive"))
    )
    (net (code "81") (name "Net-(VR15-CW)") (class "Default")
      (node (ref "R28") (pin "1") (pinfunction "1_1") (pintype "passive"))
      (node (ref "VR15") (pin "3") (pinfunction "CW_3") (pintype "passive"))
    )
    (net (code "82") (name "unconnected-(R58-Pad2)") (class "Default")
      (node (ref "R58") (pin "2") (pinfunction "2_2") (pintype "passive"))
    )
    (net (code "83") (name "unconnected-(U11-ENABLE2-Pad11)") (class "Default")
      (node (ref "U11") (pin "11") (pinfunction "ENABLE2_11") (pintype "input"))
    )
    (net (code "84") (name "unconnected-(U11-INPUT1-Pad2)") (class "Default")
      (node (ref "U11") (pin "2") (pinfunction "INPUT1_2") (pintype "input"))
    )
    (net (code "85") (name "unconnected-(U11-INPUT3-Pad12)") (class "Default")
      (node (ref "U11") (pin "12") (pinfunction "INPUT3_12") (pintype "input"))
    )
    (net (code "86") (name "unconnected-(U11-INPUT4-Pad19)") (class "Default")
      (node (ref "U11") (pin "19") (pinfunction "INPUT4_19") (pintype "input"))
    )
    (net (code "87") (name "unconnected-(U11-OUTPUT3-Pad13)") (class "Default")
      (node (ref "U11") (pin "13") (pinfunction "OUTPUT3_13") (pintype "output"))
    )
    (net (code "88") (name "unconnected-(U11-OUTPUT4-Pad18)") (class "Default")
      (node (ref "U11") (pin "18") (pinfunction "OUTPUT4_18") (pintype "output"))
    )
    (net (code "89") (name "unconnected-(VR2-CCW-Pad1)") (class "Default")
      (node (ref "VR2") (pin "1") (pinfunction "CCW_1") (pintype "passive"))
    )
    (net (code "90") (name "unconnected-(VR3-CCW-Pad1)") (class "Default")
      (node (ref "VR3") (pin "1") (pinfunction "CCW_1") (pintype "passive"))
    )
    (net (code "91") (name "unconnected-(VR4-CCW-Pad1)") (class "Default")
      (node (ref "VR4") (pin "1") (pinfunction "CCW_1") (pintype "passive"))
    )
    (net (code "92") (name "unconnected-(VR6-CCW-Pad1)") (class "Default")
      (node (ref "VR6") (pin "1") (pinfunction "CCW_1") (pintype "passive"))
    )
    (net (code "93") (name "unconnected-(VR8-CCW-Pad1)") (class "Default")
      (node (ref "VR8") (pin "1") (pinfunction "CCW_1") (pintype "passive"))
    )
    (net (code "94") (name "unconnected-(VR10-CCW-Pad1)") (class "Default")
      (node (ref "VR10") (pin "1") (pinfunction "CCW_1") (pintype "passive"))
    )
    (net (code "95") (name "unconnected-(VR12-CW-Pad3)") (class "Default")
      (node (ref "VR12") (pin "3") (pinfunction "CW_3") (pintype "passive"))
    )
    (net (code "96") (name "unconnected-(VR14-CW-Pad3)") (class "Default")
      (node (ref "VR14") (pin "3") (pinfunction "CW_3") (pintype "passive"))
    )
    (net (code "97") (name "unconnected-(VR16-CCW-Pad1)") (class "Default")
      (node (ref "VR16") (pin "1") (pinfunction "CCW_1") (pintype "passive"))
    )
  )
)
